# board.net
KiCad netlist of a schematic drawn in EAGLE
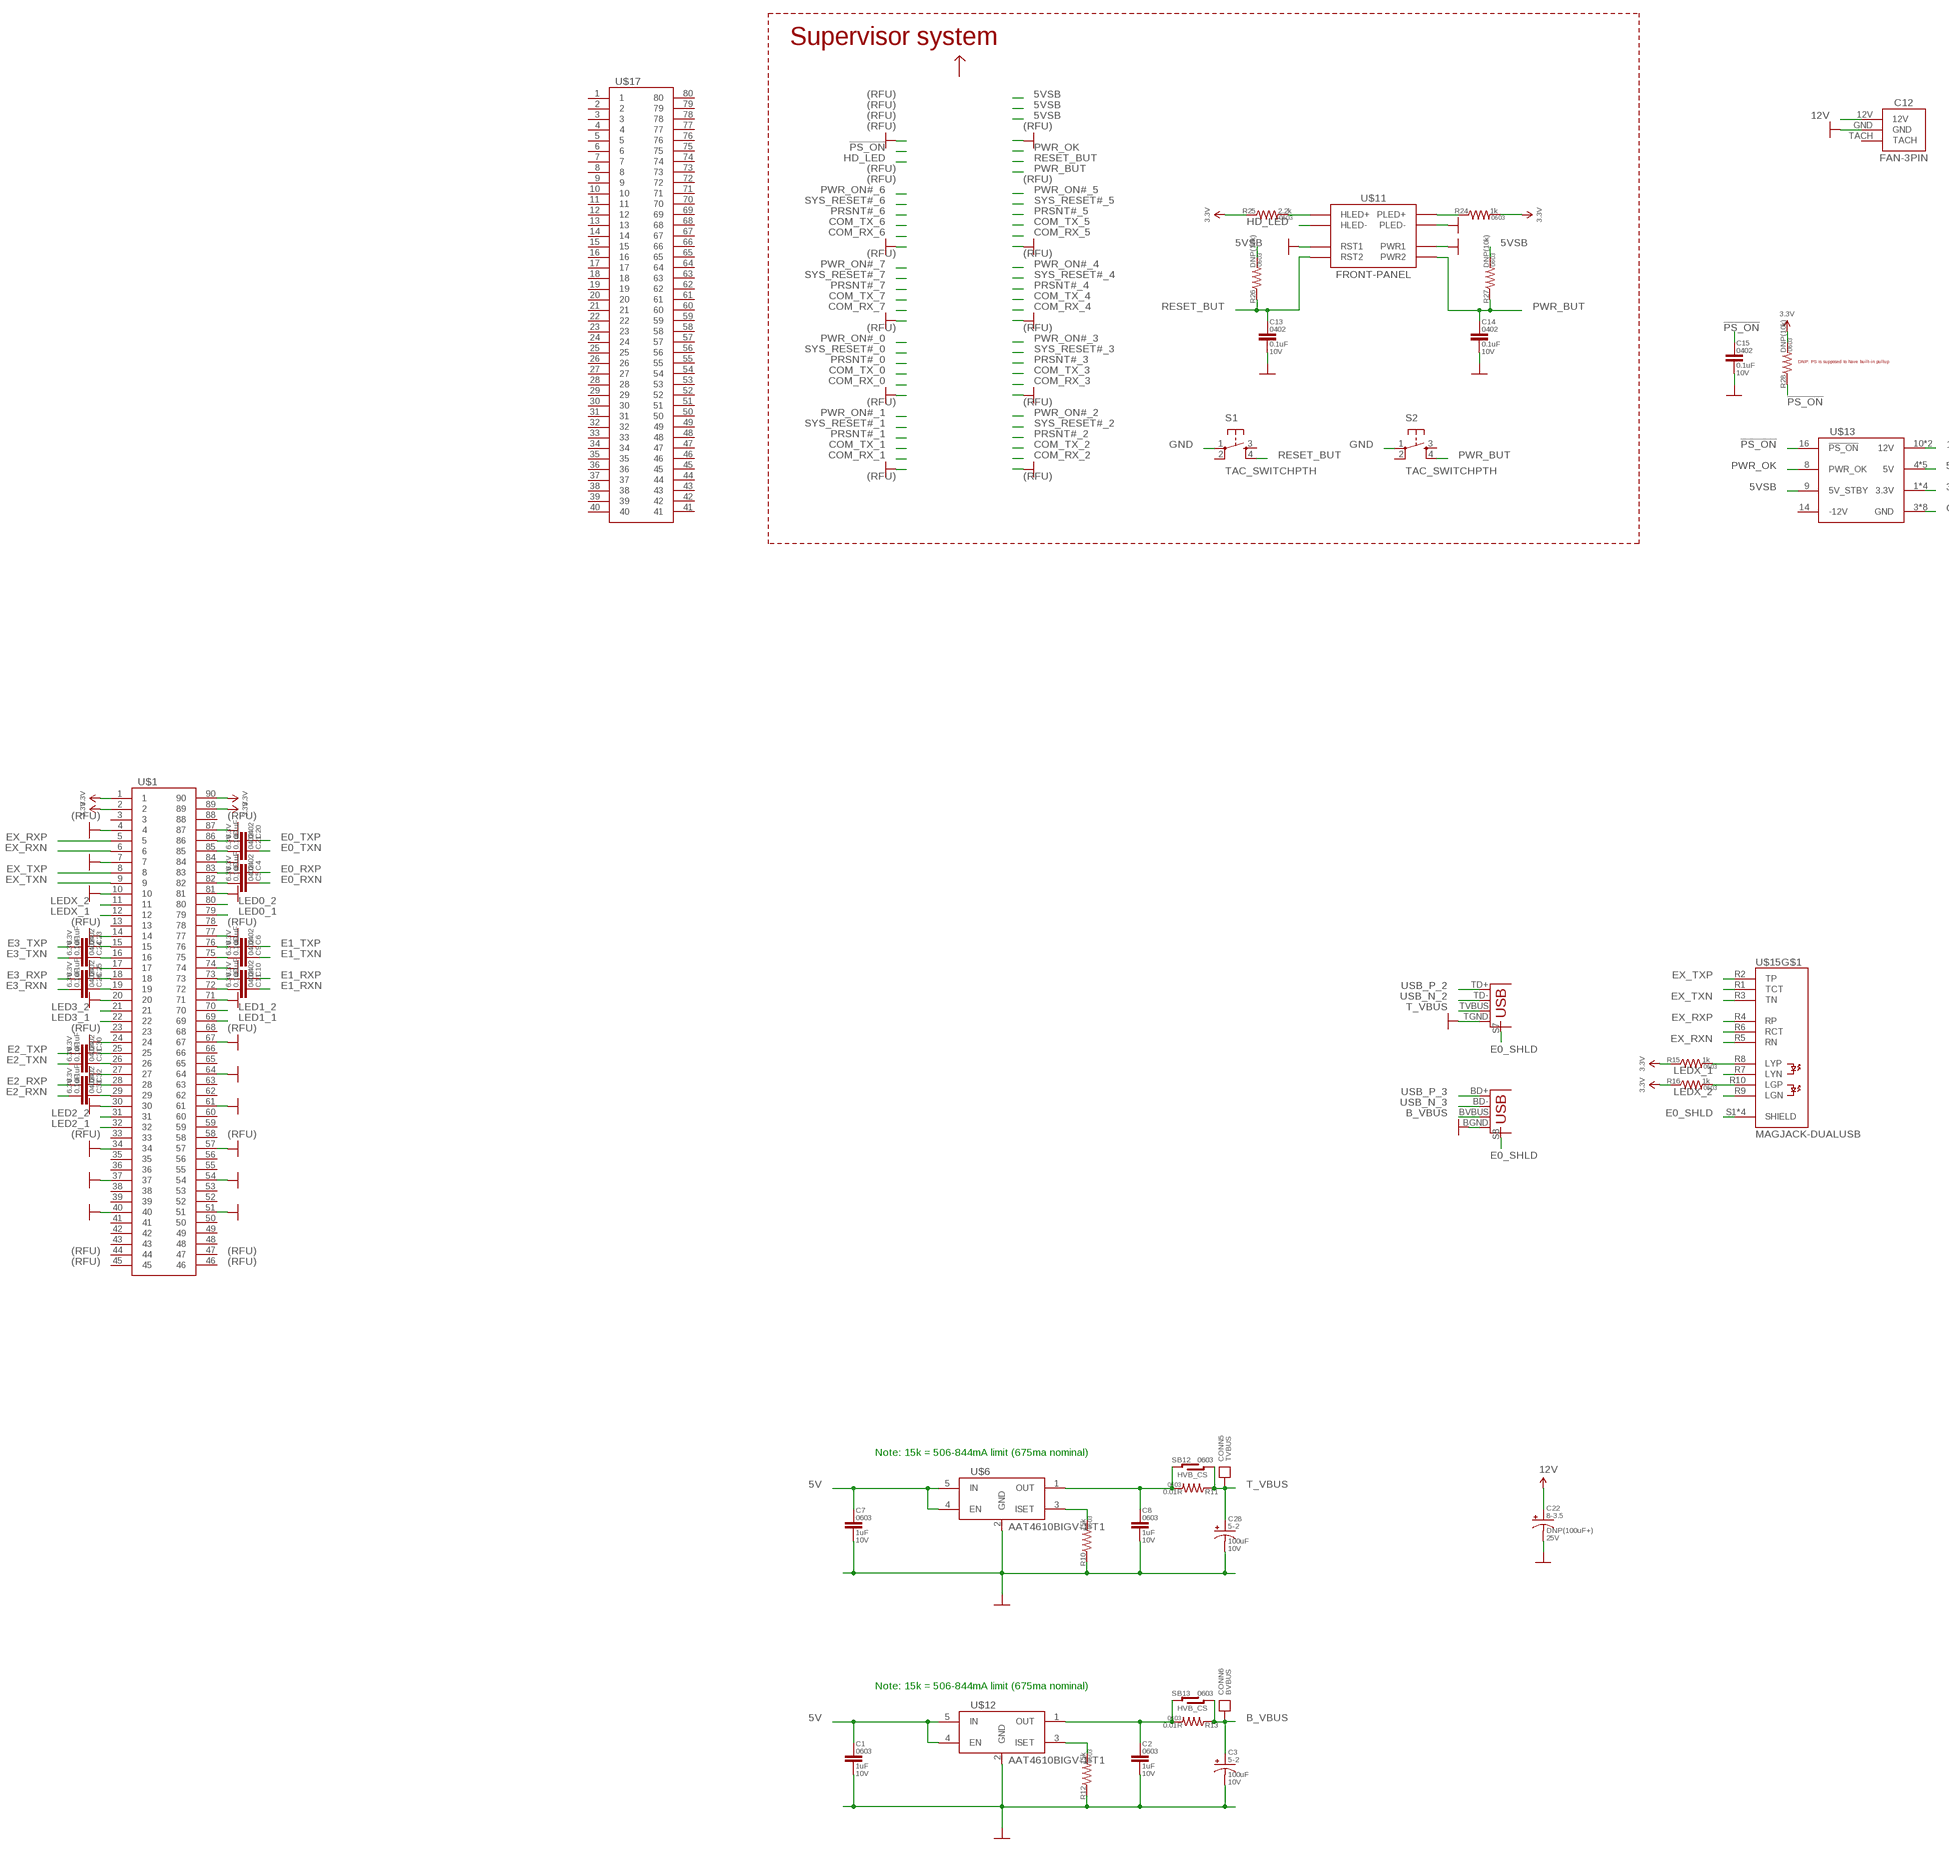
[diagram p0: schematic, sheet 1, part 1 of 2]
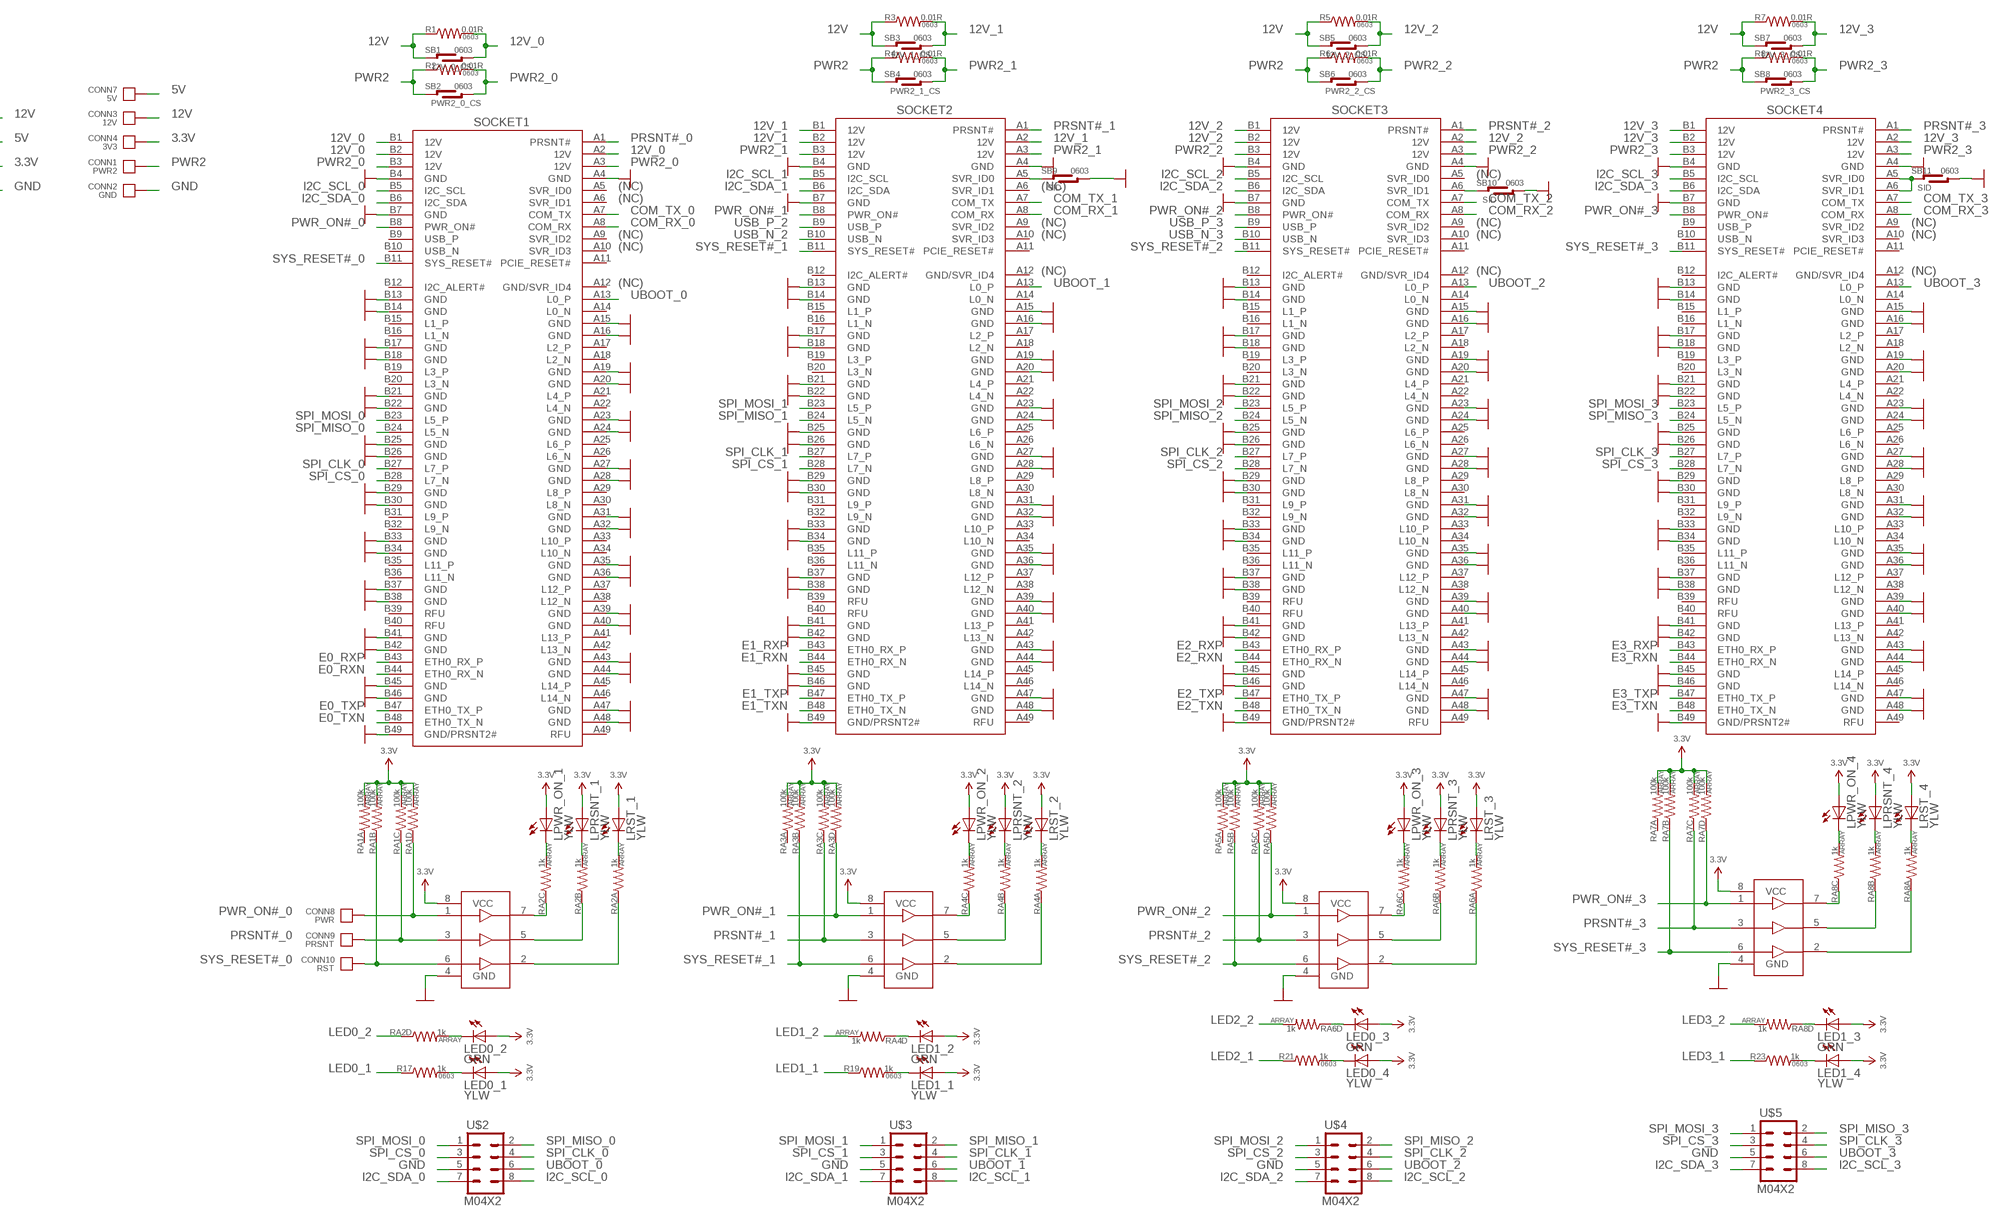
[diagram p1: schematic, sheet 1, part 2 of 2]

(export (version "E")
  (design (tool "Eeschema 10.0.6"))
  (components
    (comp (ref "C1")
      (value "1uF")
      (footprint "eagle-import:0603-CAP")
      (fields (field (name "VOLTAGE") "6.3V") (field (name "VOLTAGE_1") "10V"))
      (libsource (lib "eagle-import") (part "CAP0603"))
    )
    (comp (ref "C2")
      (value "1uF")
      (footprint "eagle-import:0603-CAP")
      (fields (field (name "VOLTAGE") "6.3V") (field (name "VOLTAGE_1") "10V"))
      (libsource (lib "eagle-import") (part "CAP0603"))
    )
    (comp (ref "C3")
      (value "100uF")
      (footprint "eagle-import:CAP-5-2")
      (fields (field (name "VOLTAGE") "6.3V") (field (name "VOLTAGE_1") "10V"))
      (libsource (lib "eagle-import") (part "CAP_POLPTH-5-2"))
    )
    (comp (ref "C4")
      (value "0.1uF")
      (footprint "eagle-import:0402-CAP")
      (fields (field (name "VOLTAGE") "6.3V"))
      (libsource (lib "eagle-import") (part "CAP0402-CAP"))
    )
    (comp (ref "C5")
      (value "0.1uF")
      (footprint "eagle-import:0402-CAP")
      (fields (field (name "VOLTAGE") "6.3V"))
      (libsource (lib "eagle-import") (part "CAP0402-CAP"))
    )
    (comp (ref "C6")
      (value "0.1uF")
      (footprint "eagle-import:0402-CAP")
      (fields (field (name "VOLTAGE") "6.3V"))
      (libsource (lib "eagle-import") (part "CAP0402-CAP"))
    )
    (comp (ref "C7")
      (value "1uF")
      (footprint "eagle-import:0603-CAP")
      (fields (field (name "VOLTAGE") "6.3V") (field (name "VOLTAGE_1") "10V"))
      (libsource (lib "eagle-import") (part "CAP0603"))
    )
    (comp (ref "C8")
      (value "1uF")
      (footprint "eagle-import:0603-CAP")
      (fields (field (name "VOLTAGE") "6.3V") (field (name "VOLTAGE_1") "10V"))
      (libsource (lib "eagle-import") (part "CAP0603"))
    )
    (comp (ref "C9")
      (value "0.1uF")
      (footprint "eagle-import:0402-CAP")
      (fields (field (name "VOLTAGE") "6.3V"))
      (libsource (lib "eagle-import") (part "CAP0402-CAP"))
    )
    (comp (ref "C10")
      (value "0.1uF")
      (footprint "eagle-import:0402-CAP")
      (fields (field (name "VOLTAGE") "6.3V"))
      (libsource (lib "eagle-import") (part "CAP0402-CAP"))
    )
    (comp (ref "C11")
      (value "0.1uF")
      (footprint "eagle-import:0402-CAP")
      (fields (field (name "VOLTAGE") "6.3V"))
      (libsource (lib "eagle-import") (part "CAP0402-CAP"))
    )
    (comp (ref "C12")
      (value "FAN-3PIN")
      (footprint "eagle-import:FAN-3PIN")
      (libsource (lib "eagle-import") (part "FAN-3PIN"))
    )
    (comp (ref "C13")
      (value "0.1uF")
      (footprint "eagle-import:0402-CAP")
      (fields (field (name "VOLTAGE") "6.3V") (field (name "VOLTAGE_1") "10V"))
      (libsource (lib "eagle-import") (part "CAP0402-CAP"))
    )
    (comp (ref "C14")
      (value "0.1uF")
      (footprint "eagle-import:0402-CAP")
      (fields (field (name "VOLTAGE") "6.3V") (field (name "VOLTAGE_1") "10V"))
      (libsource (lib "eagle-import") (part "CAP0402-CAP"))
    )
    (comp (ref "C15")
      (value "0.1uF")
      (footprint "eagle-import:0402-CAP")
      (fields (field (name "VOLTAGE") "6.3V") (field (name "VOLTAGE_1") "10V"))
      (libsource (lib "eagle-import") (part "CAP0402-CAP"))
    )
    (comp (ref "C20")
      (value "0.1uF")
      (footprint "eagle-import:0402-CAP")
      (fields (field (name "VOLTAGE") "6.3V"))
      (libsource (lib "eagle-import") (part "CAP0402-CAP"))
    )
    (comp (ref "C21")
      (value "0.1uF")
      (footprint "eagle-import:0402-CAP")
      (fields (field (name "VOLTAGE") "6.3V"))
      (libsource (lib "eagle-import") (part "CAP0402-CAP"))
    )
    (comp (ref "C22")
      (value "DNP(100uF+)")
      (footprint "eagle-import:CAP-8-3.5")
      (fields (field (name "VOLTAGE") "6.3V") (field (name "VOLTAGE_1") "25V"))
      (libsource (lib "eagle-import") (part "CAP_POLPTH-8-3.5"))
    )
    (comp (ref "C23")
      (value "0.1uF")
      (footprint "eagle-import:0402-CAP")
      (fields (field (name "VOLTAGE") "6.3V"))
      (libsource (lib "eagle-import") (part "CAP0402-CAP"))
    )
    (comp (ref "C24")
      (value "0.1uF")
      (footprint "eagle-import:0402-CAP")
      (fields (field (name "VOLTAGE") "6.3V"))
      (libsource (lib "eagle-import") (part "CAP0402-CAP"))
    )
    (comp (ref "C25")
      (value "0.1uF")
      (footprint "eagle-import:0402-CAP")
      (fields (field (name "VOLTAGE") "6.3V"))
      (libsource (lib "eagle-import") (part "CAP0402-CAP"))
    )
    (comp (ref "C26")
      (value "0.1uF")
      (footprint "eagle-import:0402-CAP")
      (fields (field (name "VOLTAGE") "6.3V"))
      (libsource (lib "eagle-import") (part "CAP0402-CAP"))
    )
    (comp (ref "C28")
      (value "100uF")
      (footprint "eagle-import:CAP-5-2")
      (fields (field (name "VOLTAGE") "6.3V") (field (name "VOLTAGE_1") "10V"))
      (libsource (lib "eagle-import") (part "CAP_POLPTH-5-2"))
    )
    (comp (ref "C30")
      (value "0.1uF")
      (footprint "eagle-import:0402-CAP")
      (fields (field (name "VOLTAGE") "6.3V"))
      (libsource (lib "eagle-import") (part "CAP0402-CAP"))
    )
    (comp (ref "C31")
      (value "0.1uF")
      (footprint "eagle-import:0402-CAP")
      (fields (field (name "VOLTAGE") "6.3V"))
      (libsource (lib "eagle-import") (part "CAP0402-CAP"))
    )
    (comp (ref "C32")
      (value "0.1uF")
      (footprint "eagle-import:0402-CAP")
      (fields (field (name "VOLTAGE") "6.3V"))
      (libsource (lib "eagle-import") (part "CAP0402-CAP"))
    )
    (comp (ref "C33")
      (value "0.1uF")
      (footprint "eagle-import:0402-CAP")
      (fields (field (name "VOLTAGE") "6.3V"))
      (libsource (lib "eagle-import") (part "CAP0402-CAP"))
    )
    (comp (ref "CONN1")
      (value "PWR2")
      (footprint "eagle-import:HOLE_18AWG")
      (libsource (lib "eagle-import") (part "CONNECTOR18AWG"))
    )
    (comp (ref "CONN2")
      (value "GND")
      (footprint "eagle-import:HOLE_18AWG")
      (libsource (lib "eagle-import") (part "CONNECTOR18AWG"))
    )
    (comp (ref "CONN3")
      (value "12V")
      (footprint "eagle-import:HOLE_18AWG")
      (libsource (lib "eagle-import") (part "CONNECTOR18AWG"))
    )
    (comp (ref "CONN4")
      (value "3V3")
      (footprint "eagle-import:HOLE_18AWG")
      (libsource (lib "eagle-import") (part "CONNECTOR18AWG"))
    )
    (comp (ref "CONN5")
      (value "TVBUS")
      (footprint "eagle-import:HOLE_22AWG")
      (libsource (lib "eagle-import") (part "CONNECTOR22AWG"))
    )
    (comp (ref "CONN6")
      (value "BVBUS")
      (footprint "eagle-import:HOLE_22AWG")
      (libsource (lib "eagle-import") (part "CONNECTOR22AWG"))
    )
    (comp (ref "CONN7")
      (value "5V")
      (footprint "eagle-import:HOLE_18AWG")
      (libsource (lib "eagle-import") (part "CONNECTOR18AWG"))
    )
    (comp (ref "CONN8")
      (value "PWR")
      (footprint "eagle-import:TESTPAD-1.27")
      (libsource (lib "eagle-import") (part "CONNECTOR1.27"))
    )
    (comp (ref "CONN9")
      (value "PRSNT")
      (footprint "eagle-import:TESTPAD-1.27")
      (libsource (lib "eagle-import") (part "CONNECTOR1.27"))
    )
    (comp (ref "CONN10")
      (value "RST")
      (footprint "eagle-import:TESTPAD-1.27")
      (libsource (lib "eagle-import") (part "CONNECTOR1.27"))
    )
    (comp (ref "IC1")
      (value "74X3G34")
      (footprint "eagle-import:TSSOP8")
      (libsource (lib "eagle-import") (part "74X3G34"))
    )
    (comp (ref "IC2")
      (value "74X3G34")
      (footprint "eagle-import:TSSOP8")
      (libsource (lib "eagle-import") (part "74X3G34"))
    )
    (comp (ref "IC3")
      (value "74X3G34")
      (footprint "eagle-import:TSSOP8")
      (libsource (lib "eagle-import") (part "74X3G34"))
    )
    (comp (ref "IC4")
      (value "74X3G34")
      (footprint "eagle-import:TSSOP8")
      (libsource (lib "eagle-import") (part "74X3G34"))
    )
    (comp (ref "LED0_1")
      (value "YLW")
      (footprint "eagle-import:0603_LED")
      (libsource (lib "eagle-import") (part "LED0603"))
    )
    (comp (ref "LED0_2")
      (value "GRN")
      (footprint "eagle-import:0603_LED")
      (libsource (lib "eagle-import") (part "LED0603"))
    )
    (comp (ref "LED0_3")
      (value "GRN")
      (footprint "eagle-import:0603_LED")
      (libsource (lib "eagle-import") (part "LED0603"))
    )
    (comp (ref "LED0_4")
      (value "YLW")
      (footprint "eagle-import:0603_LED")
      (libsource (lib "eagle-import") (part "LED0603"))
    )
    (comp (ref "LED1_1")
      (value "YLW")
      (footprint "eagle-import:0603_LED")
      (libsource (lib "eagle-import") (part "LED0603"))
    )
    (comp (ref "LED1_2")
      (value "GRN")
      (footprint "eagle-import:0603_LED")
      (libsource (lib "eagle-import") (part "LED0603"))
    )
    (comp (ref "LED1_3")
      (value "GRN")
      (footprint "eagle-import:0603_LED")
      (libsource (lib "eagle-import") (part "LED0603"))
    )
    (comp (ref "LED1_4")
      (value "YLW")
      (footprint "eagle-import:0603_LED")
      (libsource (lib "eagle-import") (part "LED0603"))
    )
    (comp (ref "LPRSNT_1")
      (value "YLW")
      (footprint "eagle-import:0603_LED")
      (libsource (lib "eagle-import") (part "LED0603"))
    )
    (comp (ref "LPRSNT_2")
      (value "YLW")
      (footprint "eagle-import:0603_LED")
      (libsource (lib "eagle-import") (part "LED0603"))
    )
    (comp (ref "LPRSNT_3")
      (value "YLW")
      (footprint "eagle-import:0603_LED")
      (libsource (lib "eagle-import") (part "LED0603"))
    )
    (comp (ref "LPRSNT_4")
      (value "YLW")
      (footprint "eagle-import:0603_LED")
      (libsource (lib "eagle-import") (part "LED0603"))
    )
    (comp (ref "LPWR_ON_1")
      (value "YLW")
      (footprint "eagle-import:0603_LED")
      (libsource (lib "eagle-import") (part "LED0603"))
    )
    (comp (ref "LPWR_ON_2")
      (value "YLW")
      (footprint "eagle-import:0603_LED")
      (libsource (lib "eagle-import") (part "LED0603"))
    )
    (comp (ref "LPWR_ON_3")
      (value "YLW")
      (footprint "eagle-import:0603_LED")
      (libsource (lib "eagle-import") (part "LED0603"))
    )
    (comp (ref "LPWR_ON_4")
      (value "YLW")
      (footprint "eagle-import:0603_LED")
      (libsource (lib "eagle-import") (part "LED0603"))
    )
    (comp (ref "LRST_1")
      (value "YLW")
      (footprint "eagle-import:0603_LED")
      (libsource (lib "eagle-import") (part "LED0603"))
    )
    (comp (ref "LRST_2")
      (value "YLW")
      (footprint "eagle-import:0603_LED")
      (libsource (lib "eagle-import") (part "LED0603"))
    )
    (comp (ref "LRST_3")
      (value "YLW")
      (footprint "eagle-import:0603_LED")
      (libsource (lib "eagle-import") (part "LED0603"))
    )
    (comp (ref "LRST_4")
      (value "YLW")
      (footprint "eagle-import:0603_LED")
      (libsource (lib "eagle-import") (part "LED0603"))
    )
    (comp (ref "R1")
      (value "0.01R")
      (footprint "eagle-import:0603-RES")
      (libsource (lib "eagle-import") (part "RESISTOR0603"))
    )
    (comp (ref "R2")
      (value "0.01R")
      (footprint "eagle-import:0603-RES")
      (libsource (lib "eagle-import") (part "RESISTOR0603"))
    )
    (comp (ref "R3")
      (value "0.01R")
      (footprint "eagle-import:0603-RES")
      (libsource (lib "eagle-import") (part "RESISTOR0603"))
    )
    (comp (ref "R4")
      (value "0.01R")
      (footprint "eagle-import:0603-RES")
      (libsource (lib "eagle-import") (part "RESISTOR0603"))
    )
    (comp (ref "R5")
      (value "0.01R")
      (footprint "eagle-import:0603-RES")
      (libsource (lib "eagle-import") (part "RESISTOR0603"))
    )
    (comp (ref "R6")
      (value "0.01R")
      (footprint "eagle-import:0603-RES")
      (libsource (lib "eagle-import") (part "RESISTOR0603"))
    )
    (comp (ref "R7")
      (value "0.01R")
      (footprint "eagle-import:0603-RES")
      (libsource (lib "eagle-import") (part "RESISTOR0603"))
    )
    (comp (ref "R8")
      (value "0.01R")
      (footprint "eagle-import:0603-RES")
      (libsource (lib "eagle-import") (part "RESISTOR0603"))
    )
    (comp (ref "R10")
      (value "15k")
      (footprint "eagle-import:0603-RES")
      (libsource (lib "eagle-import") (part "RESISTOR0603"))
    )
    (comp (ref "R11")
      (value "0.01R")
      (footprint "eagle-import:0603-RES")
      (libsource (lib "eagle-import") (part "RESISTOR0603"))
    )
    (comp (ref "R12")
      (value "15k")
      (footprint "eagle-import:0603-RES")
      (libsource (lib "eagle-import") (part "RESISTOR0603"))
    )
    (comp (ref "R13")
      (value "0.01R")
      (footprint "eagle-import:0603-RES")
      (libsource (lib "eagle-import") (part "RESISTOR0603"))
    )
    (comp (ref "R15")
      (value "1k")
      (footprint "eagle-import:0603-RES")
      (libsource (lib "eagle-import") (part "RESISTOR0603"))
    )
    (comp (ref "R16")
      (value "1k")
      (footprint "eagle-import:0603-RES")
      (libsource (lib "eagle-import") (part "RESISTOR0603"))
    )
    (comp (ref "R17")
      (value "1k")
      (footprint "eagle-import:0603-RES")
      (libsource (lib "eagle-import") (part "RESISTOR0603"))
    )
    (comp (ref "R19")
      (value "1k")
      (footprint "eagle-import:0603-RES")
      (libsource (lib "eagle-import") (part "RESISTOR0603"))
    )
    (comp (ref "R21")
      (value "1k")
      (footprint "eagle-import:0603-RES")
      (libsource (lib "eagle-import") (part "RESISTOR0603"))
    )
    (comp (ref "R23")
      (value "1k")
      (footprint "eagle-import:0603-RES")
      (libsource (lib "eagle-import") (part "RESISTOR0603"))
    )
    (comp (ref "R24")
      (value "1k")
      (footprint "eagle-import:0603-RES")
      (libsource (lib "eagle-import") (part "RESISTOR0603"))
    )
    (comp (ref "R25")
      (value "2.2k")
      (footprint "eagle-import:0603-RES")
      (libsource (lib "eagle-import") (part "RESISTOR0603"))
    )
    (comp (ref "R26")
      (value "DNP(10k)")
      (footprint "eagle-import:0603-RES")
      (libsource (lib "eagle-import") (part "RESISTOR0603"))
    )
    (comp (ref "R27")
      (value "DNP(10k)")
      (footprint "eagle-import:0603-RES")
      (libsource (lib "eagle-import") (part "RESISTOR0603"))
    )
    (comp (ref "R28")
      (value "DNP(10k)")
      (footprint "eagle-import:0603-RES")
      (libsource (lib "eagle-import") (part "RESISTOR0603"))
    )
    (comp (ref "RA1")
      (value "100k")
      (footprint "eagle-import:0603-ARV")
      (libsource (lib "eagle-import") (part "RESISTOR_ARRAY0603_X4"))
    )
    (comp (ref "RA2")
      (value "1k")
      (footprint "eagle-import:0603-ARV")
      (libsource (lib "eagle-import") (part "RESISTOR_ARRAY0603_X4"))
    )
    (comp (ref "RA3")
      (value "100k")
      (footprint "eagle-import:0603-ARV")
      (libsource (lib "eagle-import") (part "RESISTOR_ARRAY0603_X4"))
    )
    (comp (ref "RA4")
      (value "1k")
      (footprint "eagle-import:0603-ARV")
      (libsource (lib "eagle-import") (part "RESISTOR_ARRAY0603_X4"))
    )
    (comp (ref "RA5")
      (value "100k")
      (footprint "eagle-import:0603-ARV")
      (libsource (lib "eagle-import") (part "RESISTOR_ARRAY0603_X4"))
    )
    (comp (ref "RA6")
      (value "1k")
      (footprint "eagle-import:0603-ARV")
      (libsource (lib "eagle-import") (part "RESISTOR_ARRAY0603_X4"))
    )
    (comp (ref "RA7")
      (value "100k")
      (footprint "eagle-import:0603-ARV")
      (libsource (lib "eagle-import") (part "RESISTOR_ARRAY0603_X4"))
    )
    (comp (ref "RA8")
      (value "1k")
      (footprint "eagle-import:0603-ARV")
      (libsource (lib "eagle-import") (part "RESISTOR_ARRAY0603_X4"))
    )
    (comp (ref "S1")
      (value "TAC_SWITCHPTH")
      (footprint "eagle-import:TACTILE-PTH")
      (libsource (lib "eagle-import") (part "TAC_SWITCHPTH"))
    )
    (comp (ref "S2")
      (value "TAC_SWITCHPTH")
      (footprint "eagle-import:TACTILE-PTH")
      (libsource (lib "eagle-import") (part "TAC_SWITCHPTH"))
    )
    (comp (ref "SB1")
      (value "12V_0_CS")
      (footprint "eagle-import:SB-0603")
      (libsource (lib "eagle-import") (part "SOLDER-BRIDGE0603"))
    )
    (comp (ref "SB2")
      (value "PWR2_0_CS")
      (footprint "eagle-import:SB-0603")
      (libsource (lib "eagle-import") (part "SOLDER-BRIDGE0603"))
    )
    (comp (ref "SB3")
      (value "12V_1_CS")
      (footprint "eagle-import:SB-0603")
      (libsource (lib "eagle-import") (part "SOLDER-BRIDGE0603"))
    )
    (comp (ref "SB4")
      (value "PWR2_1_CS")
      (footprint "eagle-import:SB-0603")
      (libsource (lib "eagle-import") (part "SOLDER-BRIDGE0603"))
    )
    (comp (ref "SB5")
      (value "12V_2_CS")
      (footprint "eagle-import:SB-0603")
      (libsource (lib "eagle-import") (part "SOLDER-BRIDGE0603"))
    )
    (comp (ref "SB6")
      (value "PWR2_2_CS")
      (footprint "eagle-import:SB-0603")
      (libsource (lib "eagle-import") (part "SOLDER-BRIDGE0603"))
    )
    (comp (ref "SB7")
      (value "12V_3_CS")
      (footprint "eagle-import:SB-0603")
      (libsource (lib "eagle-import") (part "SOLDER-BRIDGE0603"))
    )
    (comp (ref "SB8")
      (value "PWR2_3_CS")
      (footprint "eagle-import:SB-0603")
      (libsource (lib "eagle-import") (part "SOLDER-BRIDGE0603"))
    )
    (comp (ref "SB9")
      (value "SID")
      (footprint "eagle-import:SB-0603")
      (libsource (lib "eagle-import") (part "SOLDER-BRIDGE0603"))
    )
    (comp (ref "SB10")
      (value "SID")
      (footprint "eagle-import:SB-0603")
      (libsource (lib "eagle-import") (part "SOLDER-BRIDGE0603"))
    )
    (comp (ref "SB11")
      (value "SID")
      (footprint "eagle-import:SB-0603")
      (libsource (lib "eagle-import") (part "SOLDER-BRIDGE0603"))
    )
    (comp (ref "SB12")
      (value "HVB_CS")
      (footprint "eagle-import:SB-0603")
      (libsource (lib "eagle-import") (part "SOLDER-BRIDGE0603"))
    )
    (comp (ref "SB13")
      (value "HVB_CS")
      (footprint "eagle-import:SB-0603")
      (libsource (lib "eagle-import") (part "SOLDER-BRIDGE0603"))
    )
    (comp (ref "SOCKET1")
      (value "COVEN-V1CONN")
      (footprint "eagle-import:CVN-V1-CONN")
      (libsource (lib "eagle-import") (part "COVEN-V1CONN"))
    )
    (comp (ref "SOCKET2")
      (value "COVEN-V1CONN")
      (footprint "eagle-import:CVN-V1-CONN")
      (libsource (lib "eagle-import") (part "COVEN-V1CONN"))
    )
    (comp (ref "SOCKET3")
      (value "COVEN-V1CONN")
      (footprint "eagle-import:CVN-V1-CONN")
      (libsource (lib "eagle-import") (part "COVEN-V1CONN"))
    )
    (comp (ref "SOCKET4")
      (value "COVEN-V1CONN")
      (footprint "eagle-import:CVN-V1-CONN")
      (libsource (lib "eagle-import") (part "COVEN-V1CONN"))
    )
    (comp (ref "U$1")
      (value "DF40-90RCP")
      (footprint "eagle-import:DF40-RCP-90")
      (libsource (lib "eagle-import") (part "DF40-90RCP"))
    )
    (comp (ref "U$2")
      (value "M04X2")
      (footprint "eagle-import:2X4")
      (libsource (lib "eagle-import") (part "M04X2"))
    )
    (comp (ref "U$3")
      (value "M04X2")
      (footprint "eagle-import:2X4")
      (libsource (lib "eagle-import") (part "M04X2"))
    )
    (comp (ref "U$4")
      (value "M04X2")
      (footprint "eagle-import:2X4")
      (libsource (lib "eagle-import") (part "M04X2"))
    )
    (comp (ref "U$5")
      (value "M04X2")
      (footprint "eagle-import:2X4")
      (libsource (lib "eagle-import") (part "M04X2"))
    )
    (comp (ref "U$6")
      (value "AAT4610BIGV-1-T1")
      (footprint "eagle-import:SOT23-5")
      (libsource (lib "eagle-import") (part "LOAD_SWITCH_ILIMIT"))
    )
    (comp (ref "U$11")
      (value "FRONT-PANEL")
      (footprint "eagle-import:FRONT-PANEL")
      (libsource (lib "eagle-import") (part "FRONT-PANEL"))
    )
    (comp (ref "U$12")
      (value "AAT4610BIGV-1-T1")
      (footprint "eagle-import:SOT23-5")
      (libsource (lib "eagle-import") (part "LOAD_SWITCH_ILIMIT"))
    )
    (comp (ref "U$13")
      (value "ATX-PWRVERT")
      (footprint "eagle-import:ATX-24-VERT")
      (libsource (lib "eagle-import") (part "ATX-PWRVERT"))
    )
    (comp (ref "U$15")
      (value "MAGJACK-DUALUSB")
      (footprint "eagle-import:MAGJACK-DUALUSB")
      (libsource (lib "eagle-import") (part "MAGJACK-DUALUSB"))
    )
    (comp (ref "U$17")
      (value "DF40-80RCP")
      (footprint "eagle-import:DF40-RCP-80")
      (libsource (lib "eagle-import") (part "DF40-80RCP"))
    )
  )
  (nets
    (net (code "1") (name "/5V") (class "Default")
      (node (ref "C1") (pin "1") (pinfunction "1_1") (pintype "passive"))
      (node (ref "C7") (pin "1") (pinfunction "1_1") (pintype "passive"))
      (node (ref "CONN7") (pin "P$1") (pinfunction "P_P$1") (pintype "bidirectional"))
      (node (ref "U$12") (pin "4") (pinfunction "EN_4") (pintype "bidirectional"))
      (node (ref "U$12") (pin "5") (pinfunction "IN_5") (pintype "bidirectional"))
      (node (ref "U$13") (pin "21") (pinfunction "5V_21") (pintype "bidirectional"))
      (node (ref "U$13") (pin "22") (pinfunction "5V_22") (pintype "bidirectional"))
      (node (ref "U$13") (pin "23") (pinfunction "5V_23") (pintype "bidirectional"))
      (node (ref "U$13") (pin "4") (pinfunction "5V_4") (pintype "bidirectional"))
      (node (ref "U$13") (pin "6") (pinfunction "5V_6") (pintype "bidirectional"))
      (node (ref "U$6") (pin "4") (pinfunction "EN_4") (pintype "bidirectional"))
      (node (ref "U$6") (pin "5") (pinfunction "IN_5") (pintype "bidirectional"))
    )
    (net (code "2") (name "/5VSB") (class "Default")
      (node (ref "R26") (pin "2") (pinfunction "2_2") (pintype "passive"))
      (node (ref "R27") (pin "2") (pinfunction "2_2") (pintype "passive"))
      (node (ref "U$13") (pin "9") (pinfunction "5V_STBY_9") (pintype "bidirectional"))
    )
    (net (code "3") (name "/12V_0") (class "Default")
      (node (ref "R1") (pin "2") (pinfunction "2_2") (pintype "passive"))
      (node (ref "SB1") (pin "R1") (pinfunction "P$2_R1") (pintype "passive"))
      (node (ref "SB1") (pin "R2") (pinfunction "P$2_R2") (pintype "passive"))
      (node (ref "SOCKET1") (pin "A2") (pinfunction "12V_A2") (pintype "input"))
      (node (ref "SOCKET1") (pin "B1") (pinfunction "12V_B1") (pintype "input"))
      (node (ref "SOCKET1") (pin "B2") (pinfunction "12V_B2") (pintype "input"))
    )
    (net (code "4") (name "/12V_1") (class "Default")
      (node (ref "R3") (pin "2") (pinfunction "2_2") (pintype "passive"))
      (node (ref "SB3") (pin "R1") (pinfunction "P$2_R1") (pintype "passive"))
      (node (ref "SB3") (pin "R2") (pinfunction "P$2_R2") (pintype "passive"))
      (node (ref "SOCKET2") (pin "A2") (pinfunction "12V_A2") (pintype "input"))
      (node (ref "SOCKET2") (pin "B1") (pinfunction "12V_B1") (pintype "input"))
      (node (ref "SOCKET2") (pin "B2") (pinfunction "12V_B2") (pintype "input"))
    )
    (net (code "5") (name "/12V_2") (class "Default")
      (node (ref "R5") (pin "2") (pinfunction "2_2") (pintype "passive"))
      (node (ref "SB5") (pin "R1") (pinfunction "P$2_R1") (pintype "passive"))
      (node (ref "SB5") (pin "R2") (pinfunction "P$2_R2") (pintype "passive"))
      (node (ref "SOCKET3") (pin "A2") (pinfunction "12V_A2") (pintype "input"))
      (node (ref "SOCKET3") (pin "B1") (pinfunction "12V_B1") (pintype "input"))
      (node (ref "SOCKET3") (pin "B2") (pinfunction "12V_B2") (pintype "input"))
    )
    (net (code "6") (name "/12V_3") (class "Default")
      (node (ref "R7") (pin "2") (pinfunction "2_2") (pintype "passive"))
      (node (ref "SB7") (pin "R1") (pinfunction "P$2_R1") (pintype "passive"))
      (node (ref "SB7") (pin "R2") (pinfunction "P$2_R2") (pintype "passive"))
      (node (ref "SOCKET4") (pin "A2") (pinfunction "12V_A2") (pintype "input"))
      (node (ref "SOCKET4") (pin "B1") (pinfunction "12V_B1") (pintype "input"))
      (node (ref "SOCKET4") (pin "B2") (pinfunction "12V_B2") (pintype "input"))
    )
    (net (code "7") (name "/B_VBUS") (class "Default")
      (node (ref "C3") (pin "1") (pinfunction "+_1") (pintype "passive"))
      (node (ref "CONN6") (pin "P") (pinfunction "P_P") (pintype "bidirectional"))
      (node (ref "R13") (pin "1") (pinfunction "1_1") (pintype "passive"))
      (node (ref "SB13") (pin "R1") (pinfunction "P$2_R1") (pintype "passive"))
      (node (ref "SB13") (pin "R2") (pinfunction "P$2_R2") (pintype "passive"))
      (node (ref "U$15") (pin "BVBUS") (pinfunction "VBUS_BVBUS") (pintype "bidirectional"))
    )
    (net (code "8") (name "/COM_RX_0") (class "Default")
      (node (ref "SOCKET1") (pin "A8") (pinfunction "COM_RX_A8") (pintype "bidirectional"))
    )
    (net (code "9") (name "/COM_RX_1") (class "Default")
      (node (ref "SOCKET2") (pin "A8") (pinfunction "COM_RX_A8") (pintype "bidirectional"))
    )
    (net (code "10") (name "/COM_RX_2") (class "Default")
      (node (ref "SOCKET3") (pin "A8") (pinfunction "COM_RX_A8") (pintype "bidirectional"))
    )
    (net (code "11") (name "/COM_RX_3") (class "Default")
      (node (ref "SOCKET4") (pin "A8") (pinfunction "COM_RX_A8") (pintype "bidirectional"))
    )
    (net (code "16") (name "/COM_TX_0") (class "Default")
      (node (ref "SOCKET1") (pin "A7") (pinfunction "COM_TX_A7") (pintype "bidirectional"))
    )
    (net (code "17") (name "/COM_TX_1") (class "Default")
      (node (ref "SOCKET2") (pin "A7") (pinfunction "COM_TX_A7") (pintype "bidirectional"))
    )
    (net (code "18") (name "/COM_TX_2") (class "Default")
      (node (ref "SOCKET3") (pin "A7") (pinfunction "COM_TX_A7") (pintype "bidirectional"))
    )
    (net (code "19") (name "/COM_TX_3") (class "Default")
      (node (ref "SOCKET4") (pin "A7") (pinfunction "COM_TX_A7") (pintype "bidirectional"))
    )
    (net (code "24") (name "/E0_RXN") (class "Default")
      (node (ref "C5") (pin "1") (pinfunction "1_1") (pintype "passive"))
      (node (ref "SOCKET1") (pin "B44") (pinfunction "ETH0_RX_N_B44") (pintype "bidirectional"))
    )
    (net (code "25") (name "/E0_RXP") (class "Default")
      (node (ref "C4") (pin "1") (pinfunction "1_1") (pintype "passive"))
      (node (ref "SOCKET1") (pin "B43") (pinfunction "ETH0_RX_P_B43") (pintype "bidirectional"))
    )
    (net (code "26") (name "/E0_SHLD") (class "Default")
      (node (ref "U$15") (pin "S1") (pinfunction "SHIELD_S1") (pintype "bidirectional"))
      (node (ref "U$15") (pin "S2") (pinfunction "SHIELD_S2") (pintype "bidirectional"))
      (node (ref "U$15") (pin "S3") (pinfunction "SHIELD_S3") (pintype "bidirectional"))
      (node (ref "U$15") (pin "S4") (pinfunction "SHIELD_S4") (pintype "bidirectional"))
      (node (ref "U$15") (pin "S7") (pinfunction "SHELL_S7") (pintype "bidirectional"))
      (node (ref "U$15") (pin "S8") (pinfunction "SHELL_S8") (pintype "bidirectional"))
    )
    (net (code "27") (name "/E0_TXN") (class "Default")
      (node (ref "C21") (pin "1") (pinfunction "1_1") (pintype "passive"))
      (node (ref "SOCKET1") (pin "B48") (pinfunction "ETH0_TX_N_B48") (pintype "bidirectional"))
    )
    (net (code "28") (name "/E0_TXP") (class "Default")
      (node (ref "C20") (pin "1") (pinfunction "1_1") (pintype "passive"))
      (node (ref "SOCKET1") (pin "B47") (pinfunction "ETH0_TX_P_B47") (pintype "bidirectional"))
    )
    (net (code "29") (name "/E1_RXN") (class "Default")
      (node (ref "C11") (pin "1") (pinfunction "1_1") (pintype "passive"))
      (node (ref "SOCKET2") (pin "B44") (pinfunction "ETH0_RX_N_B44") (pintype "bidirectional"))
    )
    (net (code "30") (name "/E1_RXP") (class "Default")
      (node (ref "C10") (pin "1") (pinfunction "1_1") (pintype "passive"))
      (node (ref "SOCKET2") (pin "B43") (pinfunction "ETH0_RX_P_B43") (pintype "bidirectional"))
    )
    (net (code "31") (name "/E1_TXN") (class "Default")
      (node (ref "C9") (pin "1") (pinfunction "1_1") (pintype "passive"))
      (node (ref "SOCKET2") (pin "B48") (pinfunction "ETH0_TX_N_B48") (pintype "bidirectional"))
    )
    (net (code "32") (name "/E1_TXP") (class "Default")
      (node (ref "C6") (pin "1") (pinfunction "1_1") (pintype "passive"))
      (node (ref "SOCKET2") (pin "B47") (pinfunction "ETH0_TX_P_B47") (pintype "bidirectional"))
    )
    (net (code "33") (name "/E2_RXN") (class "Default")
      (node (ref "C33") (pin "2") (pinfunction "2_2") (pintype "passive"))
      (node (ref "SOCKET3") (pin "B44") (pinfunction "ETH0_RX_N_B44") (pintype "bidirectional"))
    )
    (net (code "34") (name "/E2_RXP") (class "Default")
      (node (ref "C32") (pin "2") (pinfunction "2_2") (pintype "passive"))
      (node (ref "SOCKET3") (pin "B43") (pinfunction "ETH0_RX_P_B43") (pintype "bidirectional"))
    )
    (net (code "35") (name "/E2_TXN") (class "Default")
      (node (ref "C31") (pin "2") (pinfunction "2_2") (pintype "passive"))
      (node (ref "SOCKET3") (pin "B48") (pinfunction "ETH0_TX_N_B48") (pintype "bidirectional"))
    )
    (net (code "36") (name "/E2_TXP") (class "Default")
      (node (ref "C30") (pin "2") (pinfunction "2_2") (pintype "passive"))
      (node (ref "SOCKET3") (pin "B47") (pinfunction "ETH0_TX_P_B47") (pintype "bidirectional"))
    )
    (net (code "37") (name "/E3_RXN") (class "Default")
      (node (ref "C26") (pin "2") (pinfunction "2_2") (pintype "passive"))
      (node (ref "SOCKET4") (pin "B44") (pinfunction "ETH0_RX_N_B44") (pintype "bidirectional"))
    )
    (net (code "38") (name "/E3_RXP") (class "Default")
      (node (ref "C25") (pin "2") (pinfunction "2_2") (pintype "passive"))
      (node (ref "SOCKET4") (pin "B43") (pinfunction "ETH0_RX_P_B43") (pintype "bidirectional"))
    )
    (net (code "39") (name "/E3_TXN") (class "Default")
      (node (ref "C24") (pin "2") (pinfunction "2_2") (pintype "passive"))
      (node (ref "SOCKET4") (pin "B48") (pinfunction "ETH0_TX_N_B48") (pintype "bidirectional"))
    )
    (net (code "40") (name "/E3_TXP") (class "Default")
      (node (ref "C23") (pin "2") (pinfunction "2_2") (pintype "passive"))
      (node (ref "SOCKET4") (pin "B47") (pinfunction "ETH0_TX_P_B47") (pintype "bidirectional"))
    )
    (net (code "41") (name "/EX_RXN") (class "Default")
      (node (ref "U$1") (pin "6") (pinfunction "6_6") (pintype "bidirectional"))
      (node (ref "U$15") (pin "R5") (pinfunction "RN_R5") (pintype "bidirectional"))
    )
    (net (code "42") (name "/EX_RXP") (class "Default")
      (node (ref "U$1") (pin "5") (pinfunction "5_5") (pintype "bidirectional"))
      (node (ref "U$15") (pin "R4") (pinfunction "RP_R4") (pintype "bidirectional"))
    )
    (net (code "43") (name "/EX_TXN") (class "Default")
      (node (ref "U$1") (pin "9") (pinfunction "9_9") (pintype "bidirectional"))
      (node (ref "U$15") (pin "R3") (pinfunction "TN_R3") (pintype "bidirectional"))
    )
    (net (code "44") (name "/EX_TXP") (class "Default")
      (node (ref "U$1") (pin "8") (pinfunction "8_8") (pintype "bidirectional"))
      (node (ref "U$15") (pin "R2") (pinfunction "TP_R2") (pintype "bidirectional"))
    )
    (net (code "45") (name "/HD_LED") (class "Default")
      (node (ref "U$11") (pin "HDLED-") (pinfunction "HLED-_HDLED-") (pintype "bidirectional"))
    )
    (net (code "46") (name "/I2C_SCL_0") (class "Default")
      (node (ref "SOCKET1") (pin "B5") (pinfunction "I2C_SCL_B5") (pintype "bidirectional"))
      (node (ref "U$2") (pin "8") (pinfunction "8_8") (pintype "passive"))
    )
    (net (code "47") (name "/I2C_SCL_1") (class "Default")
      (node (ref "SOCKET2") (pin "B5") (pinfunction "I2C_SCL_B5") (pintype "bidirectional"))
      (node (ref "U$3") (pin "8") (pinfunction "8_8") (pintype "passive"))
    )
    (net (code "48") (name "/I2C_SCL_2") (class "Default")
      (node (ref "SOCKET3") (pin "B5") (pinfunction "I2C_SCL_B5") (pintype "bidirectional"))
      (node (ref "U$4") (pin "8") (pinfunction "8_8") (pintype "passive"))
    )
    (net (code "49") (name "/I2C_SCL_3") (class "Default")
      (node (ref "SOCKET4") (pin "B5") (pinfunction "I2C_SCL_B5") (pintype "bidirectional"))
      (node (ref "U$5") (pin "8") (pinfunction "8_8") (pintype "passive"))
    )
    (net (code "50") (name "/I2C_SDA_0") (class "Default")
      (node (ref "SOCKET1") (pin "B6") (pinfunction "I2C_SDA_B6") (pintype "bidirectional"))
      (node (ref "U$2") (pin "7") (pinfunction "7_7") (pintype "passive"))
    )
    (net (code "51") (name "/I2C_SDA_1") (class "Default")
      (node (ref "SOCKET2") (pin "B6") (pinfunction "I2C_SDA_B6") (pintype "bidirectional"))
      (node (ref "U$3") (pin "7") (pinfunction "7_7") (pintype "passive"))
    )
    (net (code "52") (name "/I2C_SDA_2") (class "Default")
      (node (ref "SOCKET3") (pin "B6") (pinfunction "I2C_SDA_B6") (pintype "bidirectional"))
      (node (ref "U$4") (pin "7") (pinfunction "7_7") (pintype "passive"))
    )
    (net (code "53") (name "/I2C_SDA_3") (class "Default")
      (node (ref "SOCKET4") (pin "B6") (pinfunction "I2C_SDA_B6") (pintype "bidirectional"))
      (node (ref "U$5") (pin "7") (pinfunction "7_7") (pintype "passive"))
    )
    (net (code "54") (name "/LED0_1") (class "Default")
      (node (ref "R17") (pin "1") (pinfunction "1_1") (pintype "passive"))
      (node (ref "U$1") (pin "79") (pinfunction "79_79") (pintype "bidirectional"))
    )
    (net (code "55") (name "/LED0_2") (class "Default")
      (node (ref "RA2") (pin "4") (pinfunction "1_4") (pintype "passive"))
      (node (ref "U$1") (pin "80") (pinfunction "80_80") (pintype "bidirectional"))
    )
    (net (code "56") (name "/LED1_1") (class "Default")
      (node (ref "R19") (pin "1") (pinfunction "1_1") (pintype "passive"))
      (node (ref "U$1") (pin "69") (pinfunction "69_69") (pintype "bidirectional"))
    )
    (net (code "57") (name "/LED1_2") (class "Default")
      (node (ref "RA4") (pin "5") (pinfunction "2_5") (pintype "passive"))
      (node (ref "U$1") (pin "70") (pinfunction "70_70") (pintype "bidirectional"))
    )
    (net (code "58") (name "/LED2_1") (class "Default")
      (node (ref "R21") (pin "1") (pinfunction "1_1") (pintype "passive"))
      (node (ref "U$1") (pin "32") (pinfunction "32_32") (pintype "bidirectional"))
    )
    (net (code "59") (name "/LED2_2") (class "Default")
      (node (ref "RA6") (pin "5") (pinfunction "2_5") (pintype "passive"))
      (node (ref "U$1") (pin "31") (pinfunction "31_31") (pintype "bidirectional"))
    )
    (net (code "60") (name "/LED3_1") (class "Default")
      (node (ref "R23") (pin "1") (pinfunction "1_1") (pintype "passive"))
      (node (ref "U$1") (pin "22") (pinfunction "22_22") (pintype "bidirectional"))
    )
    (net (code "61") (name "/LED3_2") (class "Default")
      (node (ref "RA8") (pin "5") (pinfunction "2_5") (pintype "passive"))
      (node (ref "U$1") (pin "21") (pinfunction "21_21") (pintype "bidirectional"))
    )
    (net (code "62") (name "/LEDX_1") (class "Default")
      (node (ref "U$1") (pin "12") (pinfunction "12_12") (pintype "bidirectional"))
      (node (ref "U$15") (pin "R7") (pinfunction "LYN_R7") (pintype "bidirectional"))
    )
    (net (code "63") (name "/LEDX_2") (class "Default")
      (node (ref "U$1") (pin "11") (pinfunction "11_11") (pintype "bidirectional"))
      (node (ref "U$15") (pin "R9") (pinfunction "LGN_R9") (pintype "bidirectional"))
    )
    (net (code "64") (name "/PRSNT#_0") (class "Default")
      (node (ref "CONN9") (pin "P") (pinfunction "P_P") (pintype "bidirectional"))
      (node (ref "IC1") (pin "3") (pinfunction "2A_3") (pintype "bidirectional"))
      (node (ref "RA1") (pin "3") (pinfunction "1_3") (pintype "passive"))
      (node (ref "SOCKET1") (pin "A1") (pinfunction "PRSNT#_A1") (pintype "bidirectional"))
    )
    (net (code "65") (name "/PRSNT#_1") (class "Default")
      (node (ref "IC2") (pin "3") (pinfunction "2A_3") (pintype "bidirectional"))
      (node (ref "RA3") (pin "3") (pinfunction "1_3") (pintype "passive"))
      (node (ref "SOCKET2") (pin "A1") (pinfunction "PRSNT#_A1") (pintype "bidirectional"))
    )
    (net (code "66") (name "/PRSNT#_2") (class "Default")
      (node (ref "IC3") (pin "3") (pinfunction "2A_3") (pintype "bidirectional"))
      (node (ref "RA5") (pin "3") (pinfunction "1_3") (pintype "passive"))
      (node (ref "SOCKET3") (pin "A1") (pinfunction "PRSNT#_A1") (pintype "bidirectional"))
    )
    (net (code "67") (name "/PRSNT#_3") (class "Default")
      (node (ref "IC4") (pin "3") (pinfunction "2A_3") (pintype "bidirectional"))
      (node (ref "RA7") (pin "3") (pinfunction "1_3") (pintype "passive"))
      (node (ref "SOCKET4") (pin "A1") (pinfunction "PRSNT#_A1") (pintype "bidirectional"))
    )
    (net (code "72") (name "/PWR2") (class "Default")
      (node (ref "CONN1") (pin "P$1") (pinfunction "P_P$1") (pintype "bidirectional"))
      (node (ref "R2") (pin "1") (pinfunction "1_1") (pintype "passive"))
      (node (ref "R4") (pin "1") (pinfunction "1_1") (pintype "passive"))
      (node (ref "R6") (pin "1") (pinfunction "1_1") (pintype "passive"))
      (node (ref "R8") (pin "1") (pinfunction "1_1") (pintype "passive"))
      (node (ref "SB2") (pin "L1") (pinfunction "P$1_L1") (pintype "passive"))
      (node (ref "SB2") (pin "L2") (pinfunction "P$1_L2") (pintype "passive"))
      (node (ref "SB4") (pin "L1") (pinfunction "P$1_L1") (pintype "passive"))
      (node (ref "SB4") (pin "L2") (pinfunction "P$1_L2") (pintype "passive"))
      (node (ref "SB6") (pin "L1") (pinfunction "P$1_L1") (pintype "passive"))
      (node (ref "SB6") (pin "L2") (pinfunction "P$1_L2") (pintype "passive"))
      (node (ref "SB8") (pin "L1") (pinfunction "P$1_L1") (pintype "passive"))
      (node (ref "SB8") (pin "L2") (pinfunction "P$1_L2") (pintype "passive"))
    )
    (net (code "73") (name "/PWR2_0") (class "Default")
      (node (ref "R2") (pin "2") (pinfunction "2_2") (pintype "passive"))
      (node (ref "SB2") (pin "R1") (pinfunction "P$2_R1") (pintype "passive"))
      (node (ref "SB2") (pin "R2") (pinfunction "P$2_R2") (pintype "passive"))
      (node (ref "SOCKET1") (pin "A3") (pinfunction "12V_A3") (pintype "input"))
      (node (ref "SOCKET1") (pin "B3") (pinfunction "12V_B3") (pintype "input"))
    )
    (net (code "74") (name "/PWR2_1") (class "Default")
      (node (ref "R4") (pin "2") (pinfunction "2_2") (pintype "passive"))
      (node (ref "SB4") (pin "R1") (pinfunction "P$2_R1") (pintype "passive"))
      (node (ref "SB4") (pin "R2") (pinfunction "P$2_R2") (pintype "passive"))
      (node (ref "SOCKET2") (pin "A3") (pinfunction "12V_A3") (pintype "input"))
      (node (ref "SOCKET2") (pin "B3") (pinfunction "12V_B3") (pintype "input"))
    )
    (net (code "75") (name "/PWR2_2") (class "Default")
      (node (ref "R6") (pin "2") (pinfunction "2_2") (pintype "passive"))
      (node (ref "SB6") (pin "R1") (pinfunction "P$2_R1") (pintype "passive"))
      (node (ref "SB6") (pin "R2") (pinfunction "P$2_R2") (pintype "passive"))
      (node (ref "SOCKET3") (pin "A3") (pinfunction "12V_A3") (pintype "input"))
      (node (ref "SOCKET3") (pin "B3") (pinfunction "12V_B3") (pintype "input"))
    )
    (net (code "76") (name "/PWR2_3") (class "Default")
      (node (ref "R8") (pin "2") (pinfunction "2_2") (pintype "passive"))
      (node (ref "SB8") (pin "R1") (pinfunction "P$2_R1") (pintype "passive"))
      (node (ref "SB8") (pin "R2") (pinfunction "P$2_R2") (pintype "passive"))
      (node (ref "SOCKET4") (pin "A3") (pinfunction "12V_A3") (pintype "input"))
      (node (ref "SOCKET4") (pin "B3") (pinfunction "12V_B3") (pintype "input"))
    )
    (net (code "77") (name "/PWR_BUT") (class "Default")
      (node (ref "C14") (pin "1") (pinfunction "1_1") (pintype "passive"))
      (node (ref "R27") (pin "1") (pinfunction "1_1") (pintype "passive"))
      (node (ref "S2") (pin "4") (pinfunction "4_4") (pintype "passive"))
      (node (ref "U$11") (pin "PWR_2") (pinfunction "PWR2_PWR_2") (pintype "bidirectional"))
    )
    (net (code "78") (name "/PWR_OK") (class "Default")
      (node (ref "U$13") (pin "8") (pinfunction "PWR_OK_8") (pintype "bidirectional"))
    )
    (net (code "79") (name "/PWR_ON#_0") (class "Default")
      (node (ref "CONN8") (pin "P") (pinfunction "P_P") (pintype "bidirectional"))
      (node (ref "IC1") (pin "1") (pinfunction "1A_1") (pintype "bidirectional"))
      (node (ref "RA1") (pin "4") (pinfunction "1_4") (pintype "passive"))
      (node (ref "SOCKET1") (pin "B8") (pinfunction "PWR_ON#_B8") (pintype "bidirectional"))
    )
    (net (code "80") (name "/PWR_ON#_1") (class "Default")
      (node (ref "IC2") (pin "1") (pinfunction "1A_1") (pintype "bidirectional"))
      (node (ref "RA3") (pin "4") (pinfunction "1_4") (pintype "passive"))
      (node (ref "SOCKET2") (pin "B8") (pinfunction "PWR_ON#_B8") (pintype "bidirectional"))
    )
    (net (code "81") (name "/PWR_ON#_2") (class "Default")
      (node (ref "IC3") (pin "1") (pinfunction "1A_1") (pintype "bidirectional"))
      (node (ref "RA5") (pin "4") (pinfunction "1_4") (pintype "passive"))
      (node (ref "SOCKET3") (pin "B8") (pinfunction "PWR_ON#_B8") (pintype "bidirectional"))
    )
    (net (code "82") (name "/PWR_ON#_3") (class "Default")
      (node (ref "IC4") (pin "1") (pinfunction "1A_1") (pintype "bidirectional"))
      (node (ref "RA7") (pin "4") (pinfunction "1_4") (pintype "passive"))
      (node (ref "SOCKET4") (pin "B8") (pinfunction "PWR_ON#_B8") (pintype "bidirectional"))
    )
    (net (code "87") (name "/RESET_BUT") (class "Default")
      (node (ref "C13") (pin "1") (pinfunction "1_1") (pintype "passive"))
      (node (ref "R26") (pin "1") (pinfunction "1_1") (pintype "passive"))
      (node (ref "S1") (pin "4") (pinfunction "4_4") (pintype "passive"))
      (node (ref "U$11") (pin "RST_2") (pinfunction "RST2_RST_2") (pintype "bidirectional"))
    )
    (net (code "88") (name "/SPI_CLK_0") (class "Default")
      (node (ref "SOCKET1") (pin "B27") (pinfunction "L7_P_B27") (pintype "bidirectional"))
      (node (ref "U$2") (pin "4") (pinfunction "4_4") (pintype "passive"))
    )
    (net (code "89") (name "/SPI_CLK_1") (class "Default")
      (node (ref "SOCKET2") (pin "B27") (pinfunction "L7_P_B27") (pintype "bidirectional"))
      (node (ref "U$3") (pin "4") (pinfunction "4_4") (pintype "passive"))
    )
    (net (code "90") (name "/SPI_CLK_2") (class "Default")
      (node (ref "SOCKET3") (pin "B27") (pinfunction "L7_P_B27") (pintype "bidirectional"))
      (node (ref "U$4") (pin "4") (pinfunction "4_4") (pintype "passive"))
    )
    (net (code "91") (name "/SPI_CLK_3") (class "Default")
      (node (ref "SOCKET4") (pin "B27") (pinfunction "L7_P_B27") (pintype "bidirectional"))
      (node (ref "U$5") (pin "4") (pinfunction "4_4") (pintype "passive"))
    )
    (net (code "92") (name "/SPI_CS_0") (class "Default")
      (node (ref "SOCKET1") (pin "B28") (pinfunction "L7_N_B28") (pintype "bidirectional"))
      (node (ref "U$2") (pin "3") (pinfunction "3_3") (pintype "passive"))
    )
    (net (code "93") (name "/SPI_CS_1") (class "Default")
      (node (ref "SOCKET2") (pin "B28") (pinfunction "L7_N_B28") (pintype "bidirectional"))
      (node (ref "U$3") (pin "3") (pinfunction "3_3") (pintype "passive"))
    )
    (net (code "94") (name "/SPI_CS_2") (class "Default")
      (node (ref "SOCKET3") (pin "B28") (pinfunction "L7_N_B28") (pintype "bidirectional"))
      (node (ref "U$4") (pin "3") (pinfunction "3_3") (pintype "passive"))
    )
    (net (code "95") (name "/SPI_CS_3") (class "Default")
      (node (ref "SOCKET4") (pin "B28") (pinfunction "L7_N_B28") (pintype "bidirectional"))
      (node (ref "U$5") (pin "3") (pinfunction "3_3") (pintype "passive"))
    )
    (net (code "96") (name "/SPI_MISO_0") (class "Default")
      (node (ref "SOCKET1") (pin "B24") (pinfunction "L5_N_B24") (pintype "bidirectional"))
      (node (ref "U$2") (pin "2") (pinfunction "2_2") (pintype "passive"))
    )
    (net (code "97") (name "/SPI_MISO_1") (class "Default")
      (node (ref "SOCKET2") (pin "B24") (pinfunction "L5_N_B24") (pintype "bidirectional"))
      (node (ref "U$3") (pin "2") (pinfunction "2_2") (pintype "passive"))
    )
    (net (code "98") (name "/SPI_MISO_2") (class "Default")
      (node (ref "SOCKET3") (pin "B24") (pinfunction "L5_N_B24") (pintype "bidirectional"))
      (node (ref "U$4") (pin "2") (pinfunction "2_2") (pintype "passive"))
    )
    (net (code "99") (name "/SPI_MISO_3") (class "Default")
      (node (ref "SOCKET4") (pin "B24") (pinfunction "L5_N_B24") (pintype "bidirectional"))
      (node (ref "U$5") (pin "2") (pinfunction "2_2") (pintype "passive"))
    )
    (net (code "100") (name "/SPI_MOSI_0") (class "Default")
      (node (ref "SOCKET1") (pin "B23") (pinfunction "L5_P_B23") (pintype "bidirectional"))
      (node (ref "U$2") (pin "1") (pinfunction "1_1") (pintype "passive"))
    )
    (net (code "101") (name "/SPI_MOSI_1") (class "Default")
      (node (ref "SOCKET2") (pin "B23") (pinfunction "L5_P_B23") (pintype "bidirectional"))
      (node (ref "U$3") (pin "1") (pinfunction "1_1") (pintype "passive"))
    )
    (net (code "102") (name "/SPI_MOSI_2") (class "Default")
      (node (ref "SOCKET3") (pin "B23") (pinfunction "L5_P_B23") (pintype "bidirectional"))
      (node (ref "U$4") (pin "1") (pinfunction "1_1") (pintype "passive"))
    )
    (net (code "103") (name "/SPI_MOSI_3") (class "Default")
      (node (ref "SOCKET4") (pin "B23") (pinfunction "L5_P_B23") (pintype "bidirectional"))
      (node (ref "U$5") (pin "1") (pinfunction "1_1") (pintype "passive"))
    )
    (net (code "104") (name "/SYS_RESET#_0") (class "Default")
      (node (ref "CONN10") (pin "P") (pinfunction "P_P") (pintype "bidirectional"))
      (node (ref "IC1") (pin "6") (pinfunction "3A_6") (pintype "bidirectional"))
      (node (ref "RA1") (pin "2") (pinfunction "1_2") (pintype "passive"))
      (node (ref "SOCKET1") (pin "B11") (pinfunction "SYS_RESET#_B11") (pintype "bidirectional"))
    )
    (net (code "105") (name "/SYS_RESET#_1") (class "Default")
      (node (ref "IC2") (pin "6") (pinfunction "3A_6") (pintype "bidirectional"))
      (node (ref "RA3") (pin "2") (pinfunction "1_2") (pintype "passive"))
      (node (ref "SOCKET2") (pin "B11") (pinfunction "SYS_RESET#_B11") (pintype "bidirectional"))
    )
    (net (code "106") (name "/SYS_RESET#_2") (class "Default")
      (node (ref "IC3") (pin "6") (pinfunction "3A_6") (pintype "bidirectional"))
      (node (ref "RA5") (pin "2") (pinfunction "1_2") (pintype "passive"))
      (node (ref "SOCKET3") (pin "B11") (pinfunction "SYS_RESET#_B11") (pintype "bidirectional"))
    )
    (net (code "107") (name "/SYS_RESET#_3") (class "Default")
      (node (ref "IC4") (pin "6") (pinfunction "3A_6") (pintype "bidirectional"))
      (node (ref "RA7") (pin "2") (pinfunction "1_2") (pintype "passive"))
      (node (ref "SOCKET4") (pin "B11") (pinfunction "SYS_RESET#_B11") (pintype "bidirectional"))
    )
    (net (code "112") (name "/T_VBUS") (class "Default")
      (node (ref "C28") (pin "1") (pinfunction "+_1") (pintype "passive"))
      (node (ref "CONN5") (pin "P") (pinfunction "P_P") (pintype "bidirectional"))
      (node (ref "R11") (pin "1") (pinfunction "1_1") (pintype "passive"))
      (node (ref "SB12") (pin "R1") (pinfunction "P$2_R1") (pintype "passive"))
      (node (ref "SB12") (pin "R2") (pinfunction "P$2_R2") (pintype "passive"))
      (node (ref "U$15") (pin "TVBUS") (pinfunction "VBUS_TVBUS") (pintype "bidirectional"))
    )
    (net (code "113") (name "/UBOOT_0") (class "Default")
      (node (ref "SOCKET1") (pin "A13") (pinfunction "L0_P_A13") (pintype "bidirectional"))
      (node (ref "U$2") (pin "6") (pinfunction "6_6") (pintype "passive"))
    )
    (net (code "114") (name "/UBOOT_1") (class "Default")
      (node (ref "SOCKET2") (pin "A13") (pinfunction "L0_P_A13") (pintype "bidirectional"))
      (node (ref "U$3") (pin "6") (pinfunction "6_6") (pintype "passive"))
    )
    (net (code "115") (name "/UBOOT_2") (class "Default")
      (node (ref "SOCKET3") (pin "A13") (pinfunction "L0_P_A13") (pintype "bidirectional"))
      (node (ref "U$4") (pin "6") (pinfunction "6_6") (pintype "passive"))
    )
    (net (code "116") (name "/UBOOT_3") (class "Default")
      (node (ref "SOCKET4") (pin "A13") (pinfunction "L0_P_A13") (pintype "bidirectional"))
      (node (ref "U$5") (pin "6") (pinfunction "6_6") (pintype "passive"))
    )
    (net (code "117") (name "/USB_N_2") (class "Default")
      (node (ref "SOCKET2") (pin "B10") (pinfunction "USB_N_B10") (pintype "bidirectional"))
      (node (ref "U$15") (pin "TD-") (pinfunction "D-_TD-") (pintype "bidirectional"))
    )
    (net (code "118") (name "/USB_N_3") (class "Default")
      (node (ref "SOCKET3") (pin "B10") (pinfunction "USB_N_B10") (pintype "bidirectional"))
      (node (ref "U$15") (pin "BD-") (pinfunction "D-_BD-") (pintype "bidirectional"))
    )
    (net (code "119") (name "/USB_P_2") (class "Default")
      (node (ref "SOCKET2") (pin "B9") (pinfunction "USB_P_B9") (pintype "bidirectional"))
      (node (ref "U$15") (pin "TD+") (pinfunction "D+_TD+") (pintype "bidirectional"))
    )
    (net (code "120") (name "/USB_P_3") (class "Default")
      (node (ref "SOCKET3") (pin "B9") (pinfunction "USB_P_B9") (pintype "bidirectional"))
      (node (ref "U$15") (pin "BD+") (pinfunction "D+_BD+") (pintype "bidirectional"))
    )
    (net (code "121") (name "/~{PS_ON}") (class "Default")
      (node (ref "C15") (pin "1") (pinfunction "1_1") (pintype "passive"))
      (node (ref "R28") (pin "1") (pinfunction "1_1") (pintype "passive"))
      (node (ref "U$13") (pin "16") (pinfunction "~{PS_ON}_16") (pintype "bidirectional"))
    )
    (net (code "122") (name "3.3V") (class "Default")
      (node (ref "CONN4") (pin "P$1") (pinfunction "P_P$1") (pintype "bidirectional"))
      (node (ref "IC1") (pin "8") (pinfunction "VCC_8") (pintype "bidirectional"))
      (node (ref "IC2") (pin "8") (pinfunction "VCC_8") (pintype "bidirectional"))
      (node (ref "IC3") (pin "8") (pinfunction "VCC_8") (pintype "bidirectional"))
      (node (ref "IC4") (pin "8") (pinfunction "VCC_8") (pintype "bidirectional"))
      (node (ref "LED0_1") (pin "A") (pinfunction "A_A") (pintype "passive"))
      (node (ref "LED0_2") (pin "A") (pinfunction "A_A") (pintype "passive"))
      (node (ref "LED0_3") (pin "A") (pinfunction "A_A") (pintype "passive"))
      (node (ref "LED0_4") (pin "A") (pinfunction "A_A") (pintype "passive"))
      (node (ref "LED1_1") (pin "A") (pinfunction "A_A") (pintype "passive"))
      (node (ref "LED1_2") (pin "A") (pinfunction "A_A") (pintype "passive"))
      (node (ref "LED1_3") (pin "A") (pinfunction "A_A") (pintype "passive"))
      (node (ref "LED1_4") (pin "A") (pinfunction "A_A") (pintype "passive"))
      (node (ref "LPRSNT_1") (pin "A") (pinfunction "A_A") (pintype "passive"))
      (node (ref "LPRSNT_2") (pin "A") (pinfunction "A_A") (pintype "passive"))
      (node (ref "LPRSNT_3") (pin "A") (pinfunction "A_A") (pintype "passive"))
      (node (ref "LPRSNT_4") (pin "A") (pinfunction "A_A") (pintype "passive"))
      (node (ref "LPWR_ON_1") (pin "A") (pinfunction "A_A") (pintype "passive"))
      (node (ref "LPWR_ON_2") (pin "A") (pinfunction "A_A") (pintype "passive"))
      (node (ref "LPWR_ON_3") (pin "A") (pinfunction "A_A") (pintype "passive"))
      (node (ref "LPWR_ON_4") (pin "A") (pinfunction "A_A") (pintype "passive"))
      (node (ref "LRST_1") (pin "A") (pinfunction "A_A") (pintype "passive"))
      (node (ref "LRST_2") (pin "A") (pinfunction "A_A") (pintype "passive"))
      (node (ref "LRST_3") (pin "A") (pinfunction "A_A") (pintype "passive"))
      (node (ref "LRST_4") (pin "A") (pinfunction "A_A") (pintype "passive"))
      (node (ref "R15") (pin "1") (pinfunction "1_1") (pintype "passive"))
      (node (ref "R16") (pin "1") (pinfunction "1_1") (pintype "passive"))
      (node (ref "R24") (pin "2") (pinfunction "2_2") (pintype "passive"))
      (node (ref "R25") (pin "1") (pinfunction "1_1") (pintype "passive"))
      (node (ref "R28") (pin "2") (pinfunction "2_2") (pintype "passive"))
      (node (ref "RA1") (pin "5") (pinfunction "2_5") (pintype "passive"))
      (node (ref "RA1") (pin "6") (pinfunction "2_6") (pintype "passive"))
      (node (ref "RA1") (pin "7") (pinfunction "2_7") (pintype "passive"))
      (node (ref "RA1") (pin "8") (pinfunction "2_8") (pintype "passive"))
      (node (ref "RA3") (pin "5") (pinfunction "2_5") (pintype "passive"))
      (node (ref "RA3") (pin "6") (pinfunction "2_6") (pintype "passive"))
      (node (ref "RA3") (pin "7") (pinfunction "2_7") (pintype "passive"))
      (node (ref "RA3") (pin "8") (pinfunction "2_8") (pintype "passive"))
      (node (ref "RA5") (pin "5") (pinfunction "2_5") (pintype "passive"))
      (node (ref "RA5") (pin "6") (pinfunction "2_6") (pintype "passive"))
      (node (ref "RA5") (pin "7") (pinfunction "2_7") (pintype "passive"))
      (node (ref "RA5") (pin "8") (pinfunction "2_8") (pintype "passive"))
      (node (ref "RA7") (pin "5") (pinfunction "2_5") (pintype "passive"))
      (node (ref "RA7") (pin "6") (pinfunction "2_6") (pintype "passive"))
      (node (ref "RA7") (pin "7") (pinfunction "2_7") (pintype "passive"))
      (node (ref "RA7") (pin "8") (pinfunction "2_8") (pintype "passive"))
      (node (ref "U$1") (pin "1") (pinfunction "1_1") (pintype "bidirectional"))
      (node (ref "U$1") (pin "2") (pinfunction "2_2") (pintype "bidirectional"))
      (node (ref "U$1") (pin "89") (pinfunction "89_89") (pintype "bidirectional"))
      (node (ref "U$1") (pin "90") (pinfunction "90_90") (pintype "bidirectional"))
      (node (ref "U$13") (pin "1") (pinfunction "3.3V_1") (pintype "bidirectional"))
      (node (ref "U$13") (pin "12") (pinfunction "3.3V_12") (pintype "bidirectional"))
      (node (ref "U$13") (pin "13") (pinfunction "3.3V_13") (pintype "bidirectional"))
      (node (ref "U$13") (pin "2") (pinfunction "3.3V_2") (pintype "bidirectional"))
    )
    (net (code "123") (name "12V") (class "Default")
      (node (ref "C12") (pin "12V") (pinfunction "12V_12V") (pintype "bidirectional"))
      (node (ref "C22") (pin "1") (pinfunction "+_1") (pintype "passive"))
      (node (ref "CONN3") (pin "P$1") (pinfunction "P_P$1") (pintype "bidirectional"))
      (node (ref "R1") (pin "1") (pinfunction "1_1") (pintype "passive"))
      (node (ref "R3") (pin "1") (pinfunction "1_1") (pintype "passive"))
      (node (ref "R5") (pin "1") (pinfunction "1_1") (pintype "passive"))
      (node (ref "R7") (pin "1") (pinfunction "1_1") (pintype "passive"))
      (node (ref "SB1") (pin "L1") (pinfunction "P$1_L1") (pintype "passive"))
      (node (ref "SB1") (pin "L2") (pinfunction "P$1_L2") (pintype "passive"))
      (node (ref "SB3") (pin "L1") (pinfunction "P$1_L1") (pintype "passive"))
      (node (ref "SB3") (pin "L2") (pinfunction "P$1_L2") (pintype "passive"))
      (node (ref "SB5") (pin "L1") (pinfunction "P$1_L1") (pintype "passive"))
      (node (ref "SB5") (pin "L2") (pinfunction "P$1_L2") (pintype "passive"))
      (node (ref "SB7") (pin "L1") (pinfunction "P$1_L1") (pintype "passive"))
      (node (ref "SB7") (pin "L2") (pinfunction "P$1_L2") (pintype "passive"))
      (node (ref "U$13") (pin "10") (pinfunction "12V_10") (pintype "bidirectional"))
      (node (ref "U$13") (pin "11") (pinfunction "12V_11") (pintype "bidirectional"))
    )
    (net (code "124") (name "GND") (class "Default")
      (node (ref "C1") (pin "2") (pinfunction "2_2") (pintype "passive"))
      (node (ref "C12") (pin "GND") (pinfunction "GND_GND") (pintype "bidirectional"))
      (node (ref "C13") (pin "2") (pinfunction "2_2") (pintype "passive"))
      (node (ref "C14") (pin "2") (pinfunction "2_2") (pintype "passive"))
      (node (ref "C15") (pin "2") (pinfunction "2_2") (pintype "passive"))
      (node (ref "C2") (pin "2") (pinfunction "2_2") (pintype "passive"))
      (node (ref "C22") (pin "2") (pinfunction "-_2") (pintype "passive"))
      (node (ref "C28") (pin "2") (pinfunction "-_2") (pintype "passive"))
      (node (ref "C3") (pin "2") (pinfunction "-_2") (pintype "passive"))
      (node (ref "C7") (pin "2") (pinfunction "2_2") (pintype "passive"))
      (node (ref "C8") (pin "2") (pinfunction "2_2") (pintype "passive"))
      (node (ref "CONN2") (pin "P$1") (pinfunction "P_P$1") (pintype "bidirectional"))
      (node (ref "IC1") (pin "4") (pinfunction "GND_4") (pintype "bidirectional"))
      (node (ref "IC2") (pin "4") (pinfunction "GND_4") (pintype "bidirectional"))
      (node (ref "IC3") (pin "4") (pinfunction "GND_4") (pintype "bidirectional"))
      (node (ref "IC4") (pin "4") (pinfunction "GND_4") (pintype "bidirectional"))
      (node (ref "R10") (pin "1") (pinfunction "1_1") (pintype "passive"))
      (node (ref "R12") (pin "1") (pinfunction "1_1") (pintype "passive"))
      (node (ref "S1") (pin "1") (pinfunction "1_1") (pintype "passive"))
      (node (ref "S2") (pin "1") (pinfunction "1_1") (pintype "passive"))
      (node (ref "SB10") (pin "R1") (pinfunction "P$2_R1") (pintype "passive"))
      (node (ref "SB10") (pin "R2") (pinfunction "P$2_R2") (pintype "passive"))
      (node (ref "SB11") (pin "R1") (pinfunction "P$2_R1") (pintype "passive"))
      (node (ref "SB11") (pin "R2") (pinfunction "P$2_R2") (pintype "passive"))
      (node (ref "SB9") (pin "R1") (pinfunction "P$2_R1") (pintype "passive"))
      (node (ref "SB9") (pin "R2") (pinfunction "P$2_R2") (pintype "passive"))
      (node (ref "SOCKET1") (pin "A15") (pinfunction "GND_A15") (pintype "input"))
      (node (ref "SOCKET1") (pin "A16") (pinfunction "GND_A16") (pintype "input"))
      (node (ref "SOCKET1") (pin "A19") (pinfunction "GND_A19") (pintype "input"))
      (node (ref "SOCKET1") (pin "A20") (pinfunction "GND_A20") (pintype "input"))
      (node (ref "SOCKET1") (pin "A23") (pinfunction "GND_A23") (pintype "input"))
      (node (ref "SOCKET1") (pin "A24") (pinfunction "GND_A24") (pintype "input"))
      (node (ref "SOCKET1") (pin "A27") (pinfunction "GND_A27") (pintype "input"))
      (node (ref "SOCKET1") (pin "A28") (pinfunction "GND_A28") (pintype "input"))
      (node (ref "SOCKET1") (pin "A31") (pinfunction "GND_A31") (pintype "input"))
      (node (ref "SOCKET1") (pin "A32") (pinfunction "GND_A32") (pintype "input"))
      (node (ref "SOCKET1") (pin "A35") (pinfunction "GND_A35") (pintype "input"))
      (node (ref "SOCKET1") (pin "A36") (pinfunction "GND_A36") (pintype "input"))
      (node (ref "SOCKET1") (pin "A39") (pinfunction "GND_A39") (pintype "input"))
      (node (ref "SOCKET1") (pin "A4") (pinfunction "GND_A4") (pintype "input"))
      (node (ref "SOCKET1") (pin "A40") (pinfunction "GND_A40") (pintype "input"))
      (node (ref "SOCKET1") (pin "A43") (pinfunction "GND_A43") (pintype "input"))
      (node (ref "SOCKET1") (pin "A44") (pinfunction "GND_A44") (pintype "input"))
      (node (ref "SOCKET1") (pin "A47") (pinfunction "GND_A47") (pintype "input"))
      (node (ref "SOCKET1") (pin "A48") (pinfunction "GND_A48") (pintype "input"))
      (node (ref "SOCKET1") (pin "B13") (pinfunction "GND_B13") (pintype "input"))
      (node (ref "SOCKET1") (pin "B14") (pinfunction "GND_B14") (pintype "input"))
      (node (ref "SOCKET1") (pin "B17") (pinfunction "GND_B17") (pintype "input"))
      (node (ref "SOCKET1") (pin "B18") (pinfunction "GND_B18") (pintype "input"))
      (node (ref "SOCKET1") (pin "B21") (pinfunction "GND_B21") (pintype "input"))
      (node (ref "SOCKET1") (pin "B22") (pinfunction "GND_B22") (pintype "input"))
      (node (ref "SOCKET1") (pin "B25") (pinfunction "GND_B25") (pintype "input"))
      (node (ref "SOCKET1") (pin "B26") (pinfunction "GND_B26") (pintype "input"))
      (node (ref "SOCKET1") (pin "B29") (pinfunction "GND_B29") (pintype "input"))
      (node (ref "SOCKET1") (pin "B30") (pinfunction "GND_B30") (pintype "input"))
      (node (ref "SOCKET1") (pin "B33") (pinfunction "GND_B33") (pintype "input"))
      (node (ref "SOCKET1") (pin "B34") (pinfunction "GND_B34") (pintype "input"))
      (node (ref "SOCKET1") (pin "B37") (pinfunction "GND_B37") (pintype "input"))
      (node (ref "SOCKET1") (pin "B38") (pinfunction "GND_B38") (pintype "input"))
      (node (ref "SOCKET1") (pin "B4") (pinfunction "GND_B4") (pintype "input"))
      (node (ref "SOCKET1") (pin "B41") (pinfunction "GND_B41") (pintype "input"))
      (node (ref "SOCKET1") (pin "B42") (pinfunction "GND_B42") (pintype "input"))
      (node (ref "SOCKET1") (pin "B45") (pinfunction "GND_B45") (pintype "input"))
      (node (ref "SOCKET1") (pin "B46") (pinfunction "GND_B46") (pintype "input"))
      (node (ref "SOCKET1") (pin "B49") (pinfunction "GND/PRSNT2#_B49") (pintype "input"))
      (node (ref "SOCKET1") (pin "B7") (pinfunction "GND_B7") (pintype "input"))
      (node (ref "SOCKET2") (pin "A15") (pinfunction "GND_A15") (pintype "input"))
      (node (ref "SOCKET2") (pin "A16") (pinfunction "GND_A16") (pintype "input"))
      (node (ref "SOCKET2") (pin "A19") (pinfunction "GND_A19") (pintype "input"))
      (node (ref "SOCKET2") (pin "A20") (pinfunction "GND_A20") (pintype "input"))
      (node (ref "SOCKET2") (pin "A23") (pinfunction "GND_A23") (pintype "input"))
      (node (ref "SOCKET2") (pin "A24") (pinfunction "GND_A24") (pintype "input"))
      (node (ref "SOCKET2") (pin "A27") (pinfunction "GND_A27") (pintype "input"))
      (node (ref "SOCKET2") (pin "A28") (pinfunction "GND_A28") (pintype "input"))
      (node (ref "SOCKET2") (pin "A31") (pinfunction "GND_A31") (pintype "input"))
      (node (ref "SOCKET2") (pin "A32") (pinfunction "GND_A32") (pintype "input"))
      (node (ref "SOCKET2") (pin "A35") (pinfunction "GND_A35") (pintype "input"))
      (node (ref "SOCKET2") (pin "A36") (pinfunction "GND_A36") (pintype "input"))
      (node (ref "SOCKET2") (pin "A39") (pinfunction "GND_A39") (pintype "input"))
      (node (ref "SOCKET2") (pin "A4") (pinfunction "GND_A4") (pintype "input"))
      (node (ref "SOCKET2") (pin "A40") (pinfunction "GND_A40") (pintype "input"))
      (node (ref "SOCKET2") (pin "A43") (pinfunction "GND_A43") (pintype "input"))
      (node (ref "SOCKET2") (pin "A44") (pinfunction "GND_A44") (pintype "input"))
      (node (ref "SOCKET2") (pin "A47") (pinfunction "GND_A47") (pintype "input"))
      (node (ref "SOCKET2") (pin "A48") (pinfunction "GND_A48") (pintype "input"))
      (node (ref "SOCKET2") (pin "B13") (pinfunction "GND_B13") (pintype "input"))
      (node (ref "SOCKET2") (pin "B14") (pinfunction "GND_B14") (pintype "input"))
      (node (ref "SOCKET2") (pin "B17") (pinfunction "GND_B17") (pintype "input"))
      (node (ref "SOCKET2") (pin "B18") (pinfunction "GND_B18") (pintype "input"))
      (node (ref "SOCKET2") (pin "B21") (pinfunction "GND_B21") (pintype "input"))
      (node (ref "SOCKET2") (pin "B22") (pinfunction "GND_B22") (pintype "input"))
      (node (ref "SOCKET2") (pin "B25") (pinfunction "GND_B25") (pintype "input"))
      (node (ref "SOCKET2") (pin "B26") (pinfunction "GND_B26") (pintype "input"))
      (node (ref "SOCKET2") (pin "B29") (pinfunction "GND_B29") (pintype "input"))
      (node (ref "SOCKET2") (pin "B30") (pinfunction "GND_B30") (pintype "input"))
      (node (ref "SOCKET2") (pin "B33") (pinfunction "GND_B33") (pintype "input"))
      (node (ref "SOCKET2") (pin "B34") (pinfunction "GND_B34") (pintype "input"))
      (node (ref "SOCKET2") (pin "B37") (pinfunction "GND_B37") (pintype "input"))
      (node (ref "SOCKET2") (pin "B38") (pinfunction "GND_B38") (pintype "input"))
      (node (ref "SOCKET2") (pin "B4") (pinfunction "GND_B4") (pintype "input"))
      (node (ref "SOCKET2") (pin "B41") (pinfunction "GND_B41") (pintype "input"))
      (node (ref "SOCKET2") (pin "B42") (pinfunction "GND_B42") (pintype "input"))
      (node (ref "SOCKET2") (pin "B45") (pinfunction "GND_B45") (pintype "input"))
      (node (ref "SOCKET2") (pin "B46") (pinfunction "GND_B46") (pintype "input"))
      (node (ref "SOCKET2") (pin "B49") (pinfunction "GND/PRSNT2#_B49") (pintype "input"))
      (node (ref "SOCKET2") (pin "B7") (pinfunction "GND_B7") (pintype "input"))
      (node (ref "SOCKET3") (pin "A15") (pinfunction "GND_A15") (pintype "input"))
      (node (ref "SOCKET3") (pin "A16") (pinfunction "GND_A16") (pintype "input"))
      (node (ref "SOCKET3") (pin "A19") (pinfunction "GND_A19") (pintype "input"))
      (node (ref "SOCKET3") (pin "A20") (pinfunction "GND_A20") (pintype "input"))
      (node (ref "SOCKET3") (pin "A23") (pinfunction "GND_A23") (pintype "input"))
      (node (ref "SOCKET3") (pin "A24") (pinfunction "GND_A24") (pintype "input"))
      (node (ref "SOCKET3") (pin "A27") (pinfunction "GND_A27") (pintype "input"))
      (node (ref "SOCKET3") (pin "A28") (pinfunction "GND_A28") (pintype "input"))
      (node (ref "SOCKET3") (pin "A31") (pinfunction "GND_A31") (pintype "input"))
      (node (ref "SOCKET3") (pin "A32") (pinfunction "GND_A32") (pintype "input"))
      (node (ref "SOCKET3") (pin "A35") (pinfunction "GND_A35") (pintype "input"))
      (node (ref "SOCKET3") (pin "A36") (pinfunction "GND_A36") (pintype "input"))
      (node (ref "SOCKET3") (pin "A39") (pinfunction "GND_A39") (pintype "input"))
      (node (ref "SOCKET3") (pin "A4") (pinfunction "GND_A4") (pintype "input"))
      (node (ref "SOCKET3") (pin "A40") (pinfunction "GND_A40") (pintype "input"))
      (node (ref "SOCKET3") (pin "A43") (pinfunction "GND_A43") (pintype "input"))
      (node (ref "SOCKET3") (pin "A44") (pinfunction "GND_A44") (pintype "input"))
      (node (ref "SOCKET3") (pin "A47") (pinfunction "GND_A47") (pintype "input"))
      (node (ref "SOCKET3") (pin "A48") (pinfunction "GND_A48") (pintype "input"))
      (node (ref "SOCKET3") (pin "B13") (pinfunction "GND_B13") (pintype "input"))
      (node (ref "SOCKET3") (pin "B14") (pinfunction "GND_B14") (pintype "input"))
      (node (ref "SOCKET3") (pin "B17") (pinfunction "GND_B17") (pintype "input"))
      (node (ref "SOCKET3") (pin "B18") (pinfunction "GND_B18") (pintype "input"))
      (node (ref "SOCKET3") (pin "B21") (pinfunction "GND_B21") (pintype "input"))
      (node (ref "SOCKET3") (pin "B22") (pinfunction "GND_B22") (pintype "input"))
      (node (ref "SOCKET3") (pin "B25") (pinfunction "GND_B25") (pintype "input"))
      (node (ref "SOCKET3") (pin "B26") (pinfunction "GND_B26") (pintype "input"))
      (node (ref "SOCKET3") (pin "B29") (pinfunction "GND_B29") (pintype "input"))
      (node (ref "SOCKET3") (pin "B30") (pinfunction "GND_B30") (pintype "input"))
      (node (ref "SOCKET3") (pin "B33") (pinfunction "GND_B33") (pintype "input"))
      (node (ref "SOCKET3") (pin "B34") (pinfunction "GND_B34") (pintype "input"))
      (node (ref "SOCKET3") (pin "B37") (pinfunction "GND_B37") (pintype "input"))
      (node (ref "SOCKET3") (pin "B38") (pinfunction "GND_B38") (pintype "input"))
      (node (ref "SOCKET3") (pin "B4") (pinfunction "GND_B4") (pintype "input"))
      (node (ref "SOCKET3") (pin "B41") (pinfunction "GND_B41") (pintype "input"))
      (node (ref "SOCKET3") (pin "B42") (pinfunction "GND_B42") (pintype "input"))
      (node (ref "SOCKET3") (pin "B45") (pinfunction "GND_B45") (pintype "input"))
      (node (ref "SOCKET3") (pin "B46") (pinfunction "GND_B46") (pintype "input"))
      (node (ref "SOCKET3") (pin "B49") (pinfunction "GND/PRSNT2#_B49") (pintype "input"))
      (node (ref "SOCKET3") (pin "B7") (pinfunction "GND_B7") (pintype "input"))
      (node (ref "SOCKET4") (pin "A15") (pinfunction "GND_A15") (pintype "input"))
      (node (ref "SOCKET4") (pin "A16") (pinfunction "GND_A16") (pintype "input"))
      (node (ref "SOCKET4") (pin "A19") (pinfunction "GND_A19") (pintype "input"))
      (node (ref "SOCKET4") (pin "A20") (pinfunction "GND_A20") (pintype "input"))
      (node (ref "SOCKET4") (pin "A23") (pinfunction "GND_A23") (pintype "input"))
      (node (ref "SOCKET4") (pin "A24") (pinfunction "GND_A24") (pintype "input"))
      (node (ref "SOCKET4") (pin "A27") (pinfunction "GND_A27") (pintype "input"))
      (node (ref "SOCKET4") (pin "A28") (pinfunction "GND_A28") (pintype "input"))
      (node (ref "SOCKET4") (pin "A31") (pinfunction "GND_A31") (pintype "input"))
      (node (ref "SOCKET4") (pin "A32") (pinfunction "GND_A32") (pintype "input"))
      (node (ref "SOCKET4") (pin "A35") (pinfunction "GND_A35") (pintype "input"))
      (node (ref "SOCKET4") (pin "A36") (pinfunction "GND_A36") (pintype "input"))
      (node (ref "SOCKET4") (pin "A39") (pinfunction "GND_A39") (pintype "input"))
      (node (ref "SOCKET4") (pin "A4") (pinfunction "GND_A4") (pintype "input"))
      (node (ref "SOCKET4") (pin "A40") (pinfunction "GND_A40") (pintype "input"))
      (node (ref "SOCKET4") (pin "A43") (pinfunction "GND_A43") (pintype "input"))
      (node (ref "SOCKET4") (pin "A44") (pinfunction "GND_A44") (pintype "input"))
      (node (ref "SOCKET4") (pin "A47") (pinfunction "GND_A47") (pintype "input"))
      (node (ref "SOCKET4") (pin "A48") (pinfunction "GND_A48") (pintype "input"))
      (node (ref "SOCKET4") (pin "B13") (pinfunction "GND_B13") (pintype "input"))
      (node (ref "SOCKET4") (pin "B14") (pinfunction "GND_B14") (pintype "input"))
      (node (ref "SOCKET4") (pin "B17") (pinfunction "GND_B17") (pintype "input"))
      (node (ref "SOCKET4") (pin "B18") (pinfunction "GND_B18") (pintype "input"))
      (node (ref "SOCKET4") (pin "B21") (pinfunction "GND_B21") (pintype "input"))
      (node (ref "SOCKET4") (pin "B22") (pinfunction "GND_B22") (pintype "input"))
      (node (ref "SOCKET4") (pin "B25") (pinfunction "GND_B25") (pintype "input"))
      (node (ref "SOCKET4") (pin "B26") (pinfunction "GND_B26") (pintype "input"))
      (node (ref "SOCKET4") (pin "B29") (pinfunction "GND_B29") (pintype "input"))
      (node (ref "SOCKET4") (pin "B30") (pinfunction "GND_B30") (pintype "input"))
      (node (ref "SOCKET4") (pin "B33") (pinfunction "GND_B33") (pintype "input"))
      (node (ref "SOCKET4") (pin "B34") (pinfunction "GND_B34") (pintype "input"))
      (node (ref "SOCKET4") (pin "B37") (pinfunction "GND_B37") (pintype "input"))
      (node (ref "SOCKET4") (pin "B38") (pinfunction "GND_B38") (pintype "input"))
      (node (ref "SOCKET4") (pin "B4") (pinfunction "GND_B4") (pintype "input"))
      (node (ref "SOCKET4") (pin "B41") (pinfunction "GND_B41") (pintype "input"))
      (node (ref "SOCKET4") (pin "B42") (pinfunction "GND_B42") (pintype "input"))
      (node (ref "SOCKET4") (pin "B45") (pinfunction "GND_B45") (pintype "input"))
      (node (ref "SOCKET4") (pin "B46") (pinfunction "GND_B46") (pintype "input"))
      (node (ref "SOCKET4") (pin "B49") (pinfunction "GND/PRSNT2#_B49") (pintype "input"))
      (node (ref "SOCKET4") (pin "B7") (pinfunction "GND_B7") (pintype "input"))
      (node (ref "U$1") (pin "10") (pinfunction "10_10") (pintype "bidirectional"))
      (node (ref "U$1") (pin "14") (pinfunction "14_14") (pintype "bidirectional"))
      (node (ref "U$1") (pin "17") (pinfunction "17_17") (pintype "bidirectional"))
      (node (ref "U$1") (pin "20") (pinfunction "20_20") (pintype "bidirectional"))
      (node (ref "U$1") (pin "24") (pinfunction "24_24") (pintype "bidirectional"))
      (node (ref "U$1") (pin "27") (pinfunction "27_27") (pintype "bidirectional"))
      (node (ref "U$1") (pin "30") (pinfunction "30_30") (pintype "bidirectional"))
      (node (ref "U$1") (pin "34") (pinfunction "34_34") (pintype "bidirectional"))
      (node (ref "U$1") (pin "37") (pinfunction "37_37") (pintype "bidirectional"))
      (node (ref "U$1") (pin "4") (pinfunction "4_4") (pintype "bidirectional"))
      (node (ref "U$1") (pin "40") (pinfunction "40_40") (pintype "bidirectional"))
      (node (ref "U$1") (pin "51") (pinfunction "51_51") (pintype "bidirectional"))
      (node (ref "U$1") (pin "54") (pinfunction "54_54") (pintype "bidirectional"))
      (node (ref "U$1") (pin "57") (pinfunction "57_57") (pintype "bidirectional"))
      (node (ref "U$1") (pin "61") (pinfunction "61_61") (pintype "bidirectional"))
      (node (ref "U$1") (pin "64") (pinfunction "64_64") (pintype "bidirectional"))
      (node (ref "U$1") (pin "67") (pinfunction "67_67") (pintype "bidirectional"))
      (node (ref "U$1") (pin "7") (pinfunction "7_7") (pintype "bidirectional"))
      (node (ref "U$1") (pin "71") (pinfunction "71_71") (pintype "bidirectional"))
      (node (ref "U$1") (pin "74") (pinfunction "74_74") (pintype "bidirectional"))
      (node (ref "U$1") (pin "77") (pinfunction "77_77") (pintype "bidirectional"))
      (node (ref "U$1") (pin "81") (pinfunction "81_81") (pintype "bidirectional"))
      (node (ref "U$1") (pin "84") (pinfunction "84_84") (pintype "bidirectional"))
      (node (ref "U$1") (pin "87") (pinfunction "87_87") (pintype "bidirectional"))
      (node (ref "U$11") (pin "PLED-") (pinfunction "PLED-_PLED-") (pintype "bidirectional"))
      (node (ref "U$11") (pin "PWR_1") (pinfunction "PWR1_PWR_1") (pintype "bidirectional"))
      (node (ref "U$11") (pin "RST_1") (pinfunction "RST1_RST_1") (pintype "bidirectional"))
      (node (ref "U$12") (pin "2") (pinfunction "GND_2") (pintype "bidirectional"))
      (node (ref "U$13") (pin "15") (pinfunction "GND_15") (pintype "bidirectional"))
      (node (ref "U$13") (pin "17") (pinfunction "GND_17") (pintype "bidirectional"))
      (node (ref "U$13") (pin "18") (pinfunction "GND_18") (pintype "bidirectional"))
      (node (ref "U$13") (pin "19") (pinfunction "GND_19") (pintype "bidirectional"))
      (node (ref "U$13") (pin "24") (pinfunction "GND_24") (pintype "bidirectional"))
      (node (ref "U$13") (pin "3") (pinfunction "GND_3") (pintype "bidirectional"))
      (node (ref "U$13") (pin "5") (pinfunction "GND_5") (pintype "bidirectional"))
      (node (ref "U$13") (pin "7") (pinfunction "GND_7") (pintype "bidirectional"))
      (node (ref "U$15") (pin "BGND") (pinfunction "GND_BGND") (pintype "bidirectional"))
      (node (ref "U$15") (pin "TGND") (pinfunction "GND_TGND") (pintype "bidirectional"))
      (node (ref "U$2") (pin "5") (pinfunction "5_5") (pintype "passive"))
      (node (ref "U$3") (pin "5") (pinfunction "5_5") (pintype "passive"))
      (node (ref "U$4") (pin "5") (pinfunction "5_5") (pintype "passive"))
      (node (ref "U$5") (pin "5") (pinfunction "5_5") (pintype "passive"))
      (node (ref "U$6") (pin "2") (pinfunction "GND_2") (pintype "bidirectional"))
    )
    (net (code "125") (name "Net-(C4-Pad2)") (class "Default")
      (node (ref "C4") (pin "2") (pinfunction "2_2") (pintype "passive"))
      (node (ref "U$1") (pin "83") (pinfunction "83_83") (pintype "bidirectional"))
    )
    (net (code "126") (name "Net-(C5-Pad2)") (class "Default")
      (node (ref "C5") (pin "2") (pinfunction "2_2") (pintype "passive"))
      (node (ref "U$1") (pin "82") (pinfunction "82_82") (pintype "bidirectional"))
    )
    (net (code "127") (name "Net-(C6-Pad2)") (class "Default")
      (node (ref "C6") (pin "2") (pinfunction "2_2") (pintype "passive"))
      (node (ref "U$1") (pin "76") (pinfunction "76_76") (pintype "bidirectional"))
    )
    (net (code "128") (name "Net-(C9-Pad2)") (class "Default")
      (node (ref "C9") (pin "2") (pinfunction "2_2") (pintype "passive"))
      (node (ref "U$1") (pin "75") (pinfunction "75_75") (pintype "bidirectional"))
    )
    (net (code "129") (name "Net-(C10-Pad2)") (class "Default")
      (node (ref "C10") (pin "2") (pinfunction "2_2") (pintype "passive"))
      (node (ref "U$1") (pin "73") (pinfunction "73_73") (pintype "bidirectional"))
    )
    (net (code "130") (name "Net-(C11-Pad2)") (class "Default")
      (node (ref "C11") (pin "2") (pinfunction "2_2") (pintype "passive"))
      (node (ref "U$1") (pin "72") (pinfunction "72_72") (pintype "bidirectional"))
    )
    (net (code "131") (name "Net-(C20-Pad2)") (class "Default")
      (node (ref "C20") (pin "2") (pinfunction "2_2") (pintype "passive"))
      (node (ref "U$1") (pin "86") (pinfunction "86_86") (pintype "bidirectional"))
    )
    (net (code "132") (name "Net-(C21-Pad2)") (class "Default")
      (node (ref "C21") (pin "2") (pinfunction "2_2") (pintype "passive"))
      (node (ref "U$1") (pin "85") (pinfunction "85_85") (pintype "bidirectional"))
    )
    (net (code "133") (name "Net-(C23-Pad1)") (class "Default")
      (node (ref "C23") (pin "1") (pinfunction "1_1") (pintype "passive"))
      (node (ref "U$1") (pin "15") (pinfunction "15_15") (pintype "bidirectional"))
    )
    (net (code "134") (name "Net-(C24-Pad1)") (class "Default")
      (node (ref "C24") (pin "1") (pinfunction "1_1") (pintype "passive"))
      (node (ref "U$1") (pin "16") (pinfunction "16_16") (pintype "bidirectional"))
    )
    (net (code "135") (name "Net-(C25-Pad1)") (class "Default")
      (node (ref "C25") (pin "1") (pinfunction "1_1") (pintype "passive"))
      (node (ref "U$1") (pin "18") (pinfunction "18_18") (pintype "bidirectional"))
    )
    (net (code "136") (name "Net-(C26-Pad1)") (class "Default")
      (node (ref "C26") (pin "1") (pinfunction "1_1") (pintype "passive"))
      (node (ref "U$1") (pin "19") (pinfunction "19_19") (pintype "bidirectional"))
    )
    (net (code "137") (name "Net-(C30-Pad1)") (class "Default")
      (node (ref "C30") (pin "1") (pinfunction "1_1") (pintype "passive"))
      (node (ref "U$1") (pin "25") (pinfunction "25_25") (pintype "bidirectional"))
    )
    (net (code "138") (name "Net-(C31-Pad1)") (class "Default")
      (node (ref "C31") (pin "1") (pinfunction "1_1") (pintype "passive"))
      (node (ref "U$1") (pin "26") (pinfunction "26_26") (pintype "bidirectional"))
    )
    (net (code "139") (name "Net-(C32-Pad1)") (class "Default")
      (node (ref "C32") (pin "1") (pinfunction "1_1") (pintype "passive"))
      (node (ref "U$1") (pin "28") (pinfunction "28_28") (pintype "bidirectional"))
    )
    (net (code "140") (name "Net-(C33-Pad1)") (class "Default")
      (node (ref "C33") (pin "1") (pinfunction "1_1") (pintype "passive"))
      (node (ref "U$1") (pin "29") (pinfunction "29_29") (pintype "bidirectional"))
    )
    (net (code "141") (name "Net-(IC1-1Y)") (class "Default")
      (node (ref "IC1") (pin "7") (pinfunction "1Y_7") (pintype "bidirectional"))
      (node (ref "RA2") (pin "3") (pinfunction "1_3") (pintype "passive"))
    )
    (net (code "142") (name "Net-(IC1-2Y)") (class "Default")
      (node (ref "IC1") (pin "5") (pinfunction "2Y_5") (pintype "bidirectional"))
      (node (ref "RA2") (pin "2") (pinfunction "1_2") (pintype "passive"))
    )
    (net (code "143") (name "Net-(IC1-3Y)") (class "Default")
      (node (ref "IC1") (pin "2") (pinfunction "3Y_2") (pintype "bidirectional"))
      (node (ref "RA2") (pin "1") (pinfunction "1_1") (pintype "passive"))
    )
    (net (code "144") (name "Net-(IC2-1Y)") (class "Default")
      (node (ref "IC2") (pin "7") (pinfunction "1Y_7") (pintype "bidirectional"))
      (node (ref "RA4") (pin "3") (pinfunction "1_3") (pintype "passive"))
    )
    (net (code "145") (name "Net-(IC2-2Y)") (class "Default")
      (node (ref "IC2") (pin "5") (pinfunction "2Y_5") (pintype "bidirectional"))
      (node (ref "RA4") (pin "2") (pinfunction "1_2") (pintype "passive"))
    )
    (net (code "146") (name "Net-(IC2-3Y)") (class "Default")
      (node (ref "IC2") (pin "2") (pinfunction "3Y_2") (pintype "bidirectional"))
      (node (ref "RA4") (pin "1") (pinfunction "1_1") (pintype "passive"))
    )
    (net (code "147") (name "Net-(IC3-1Y)") (class "Default")
      (node (ref "IC3") (pin "7") (pinfunction "1Y_7") (pintype "bidirectional"))
      (node (ref "RA6") (pin "3") (pinfunction "1_3") (pintype "passive"))
    )
    (net (code "148") (name "Net-(IC3-2Y)") (class "Default")
      (node (ref "IC3") (pin "5") (pinfunction "2Y_5") (pintype "bidirectional"))
      (node (ref "RA6") (pin "2") (pinfunction "1_2") (pintype "passive"))
    )
    (net (code "149") (name "Net-(IC3-3Y)") (class "Default")
      (node (ref "IC3") (pin "2") (pinfunction "3Y_2") (pintype "bidirectional"))
      (node (ref "RA6") (pin "1") (pinfunction "1_1") (pintype "passive"))
    )
    (net (code "150") (name "Net-(IC4-1Y)") (class "Default")
      (node (ref "IC4") (pin "7") (pinfunction "1Y_7") (pintype "bidirectional"))
      (node (ref "RA8") (pin "3") (pinfunction "1_3") (pintype "passive"))
    )
    (net (code "151") (name "Net-(IC4-2Y)") (class "Default")
      (node (ref "IC4") (pin "5") (pinfunction "2Y_5") (pintype "bidirectional"))
      (node (ref "RA8") (pin "2") (pinfunction "1_2") (pintype "passive"))
    )
    (net (code "152") (name "Net-(IC4-3Y)") (class "Default")
      (node (ref "IC4") (pin "2") (pinfunction "3Y_2") (pintype "bidirectional"))
      (node (ref "RA8") (pin "1") (pinfunction "1_1") (pintype "passive"))
    )
    (net (code "153") (name "Net-(LED0_1-PadC)") (class "Default")
      (node (ref "LED0_1") (pin "C") (pinfunction "C_C") (pintype "passive"))
      (node (ref "R17") (pin "2") (pinfunction "2_2") (pintype "passive"))
    )
    (net (code "154") (name "Net-(LED0_4-PadC)") (class "Default")
      (node (ref "LED0_4") (pin "C") (pinfunction "C_C") (pintype "passive"))
      (node (ref "R21") (pin "2") (pinfunction "2_2") (pintype "passive"))
    )
    (net (code "155") (name "Net-(LED1_1-PadC)") (class "Default")
      (node (ref "LED1_1") (pin "C") (pinfunction "C_C") (pintype "passive"))
      (node (ref "R19") (pin "2") (pinfunction "2_2") (pintype "passive"))
    )
    (net (code "156") (name "Net-(LED1_4-PadC)") (class "Default")
      (node (ref "LED1_4") (pin "C") (pinfunction "C_C") (pintype "passive"))
      (node (ref "R23") (pin "2") (pinfunction "2_2") (pintype "passive"))
    )
    (net (code "157") (name "Net-(R24-Pad1)") (class "Default")
      (node (ref "R24") (pin "1") (pinfunction "1_1") (pintype "passive"))
      (node (ref "U$11") (pin "PLED+") (pinfunction "PLED+_PLED+") (pintype "bidirectional"))
    )
    (net (code "158") (name "Net-(RA2A-2)") (class "Default")
      (node (ref "LRST_1") (pin "C") (pinfunction "C_C") (pintype "passive"))
      (node (ref "RA2") (pin "8") (pinfunction "2_8") (pintype "passive"))
    )
    (net (code "159") (name "Net-(RA2B-2)") (class "Default")
      (node (ref "LPRSNT_1") (pin "C") (pinfunction "C_C") (pintype "passive"))
      (node (ref "RA2") (pin "7") (pinfunction "2_7") (pintype "passive"))
    )
    (net (code "160") (name "Net-(RA2C-2)") (class "Default")
      (node (ref "LPWR_ON_1") (pin "C") (pinfunction "C_C") (pintype "passive"))
      (node (ref "RA2") (pin "6") (pinfunction "2_6") (pintype "passive"))
    )
    (net (code "161") (name "Net-(RA2D-2)") (class "Default")
      (node (ref "LED0_2") (pin "C") (pinfunction "C_C") (pintype "passive"))
      (node (ref "RA2") (pin "5") (pinfunction "2_5") (pintype "passive"))
    )
    (net (code "162") (name "Net-(RA4A-2)") (class "Default")
      (node (ref "LRST_2") (pin "C") (pinfunction "C_C") (pintype "passive"))
      (node (ref "RA4") (pin "8") (pinfunction "2_8") (pintype "passive"))
    )
    (net (code "163") (name "Net-(RA4B-2)") (class "Default")
      (node (ref "LPRSNT_2") (pin "C") (pinfunction "C_C") (pintype "passive"))
      (node (ref "RA4") (pin "7") (pinfunction "2_7") (pintype "passive"))
    )
    (net (code "164") (name "Net-(RA4C-2)") (class "Default")
      (node (ref "LPWR_ON_2") (pin "C") (pinfunction "C_C") (pintype "passive"))
      (node (ref "RA4") (pin "6") (pinfunction "2_6") (pintype "passive"))
    )
    (net (code "165") (name "Net-(RA4D-1)") (class "Default")
      (node (ref "LED1_2") (pin "C") (pinfunction "C_C") (pintype "passive"))
      (node (ref "RA4") (pin "4") (pinfunction "1_4") (pintype "passive"))
    )
    (net (code "166") (name "Net-(RA6A-2)") (class "Default")
      (node (ref "LRST_3") (pin "C") (pinfunction "C_C") (pintype "passive"))
      (node (ref "RA6") (pin "8") (pinfunction "2_8") (pintype "passive"))
    )
    (net (code "167") (name "Net-(RA6B-2)") (class "Default")
      (node (ref "LPRSNT_3") (pin "C") (pinfunction "C_C") (pintype "passive"))
      (node (ref "RA6") (pin "7") (pinfunction "2_7") (pintype "passive"))
    )
    (net (code "168") (name "Net-(RA6C-2)") (class "Default")
      (node (ref "LPWR_ON_3") (pin "C") (pinfunction "C_C") (pintype "passive"))
      (node (ref "RA6") (pin "6") (pinfunction "2_6") (pintype "passive"))
    )
    (net (code "169") (name "Net-(RA6D-1)") (class "Default")
      (node (ref "LED0_3") (pin "C") (pinfunction "C_C") (pintype "passive"))
      (node (ref "RA6") (pin "4") (pinfunction "1_4") (pintype "passive"))
    )
    (net (code "170") (name "Net-(RA8A-2)") (class "Default")
      (node (ref "LRST_4") (pin "C") (pinfunction "C_C") (pintype "passive"))
      (node (ref "RA8") (pin "8") (pinfunction "2_8") (pintype "passive"))
    )
    (net (code "171") (name "Net-(RA8B-2)") (class "Default")
      (node (ref "LPRSNT_4") (pin "C") (pinfunction "C_C") (pintype "passive"))
      (node (ref "RA8") (pin "7") (pinfunction "2_7") (pintype "passive"))
    )
    (net (code "172") (name "Net-(RA8C-2)") (class "Default")
      (node (ref "LPWR_ON_4") (pin "C") (pinfunction "C_C") (pintype "passive"))
      (node (ref "RA8") (pin "6") (pinfunction "2_6") (pintype "passive"))
    )
    (net (code "173") (name "Net-(RA8D-1)") (class "Default")
      (node (ref "LED1_3") (pin "C") (pinfunction "C_C") (pintype "passive"))
      (node (ref "RA8") (pin "4") (pinfunction "1_4") (pintype "passive"))
    )
    (net (code "174") (name "Net-(SOCKET2-SVR_ID0)") (class "Default")
      (node (ref "SB9") (pin "L1") (pinfunction "P$1_L1") (pintype "passive"))
      (node (ref "SB9") (pin "L2") (pinfunction "P$1_L2") (pintype "passive"))
      (node (ref "SOCKET2") (pin "A5") (pinfunction "SVR_ID0_A5") (pintype "bidirectional"))
    )
    (net (code "175") (name "Net-(SOCKET3-SVR_ID1)") (class "Default")
      (node (ref "SB10") (pin "L1") (pinfunction "P$1_L1") (pintype "passive"))
      (node (ref "SB10") (pin "L2") (pinfunction "P$1_L2") (pintype "passive"))
      (node (ref "SOCKET3") (pin "A6") (pinfunction "SVR_ID1_A6") (pintype "bidirectional"))
    )
    (net (code "176") (name "Net-(SOCKET4-SVR_ID0)") (class "Default")
      (node (ref "SB11") (pin "L1") (pinfunction "P$1_L1") (pintype "passive"))
      (node (ref "SB11") (pin "L2") (pinfunction "P$1_L2") (pintype "passive"))
      (node (ref "SOCKET4") (pin "A5") (pinfunction "SVR_ID0_A5") (pintype "bidirectional"))
      (node (ref "SOCKET4") (pin "A6") (pinfunction "SVR_ID1_A6") (pintype "bidirectional"))
    )
    (net (code "177") (name "Net-(U$6-ISET)") (class "Default")
      (node (ref "R10") (pin "2") (pinfunction "2_2") (pintype "passive"))
      (node (ref "U$6") (pin "3") (pinfunction "ISET_3") (pintype "bidirectional"))
    )
    (net (code "178") (name "Net-(U$6-OUT)") (class "Default")
      (node (ref "C8") (pin "1") (pinfunction "1_1") (pintype "passive"))
      (node (ref "R11") (pin "2") (pinfunction "2_2") (pintype "passive"))
      (node (ref "SB12") (pin "L1") (pinfunction "P$1_L1") (pintype "passive"))
      (node (ref "SB12") (pin "L2") (pinfunction "P$1_L2") (pintype "passive"))
      (node (ref "U$6") (pin "1") (pinfunction "OUT_1") (pintype "bidirectional"))
    )
    (net (code "179") (name "Net-(U$11-HLED+)") (class "Default")
      (node (ref "R25") (pin "2") (pinfunction "2_2") (pintype "passive"))
      (node (ref "U$11") (pin "HDLED+") (pinfunction "HLED+_HDLED+") (pintype "bidirectional"))
    )
    (net (code "180") (name "Net-(U$12-ISET)") (class "Default")
      (node (ref "R12") (pin "2") (pinfunction "2_2") (pintype "passive"))
      (node (ref "U$12") (pin "3") (pinfunction "ISET_3") (pintype "bidirectional"))
    )
    (net (code "181") (name "Net-(U$12-OUT)") (class "Default")
      (node (ref "C2") (pin "1") (pinfunction "1_1") (pintype "passive"))
      (node (ref "R13") (pin "2") (pinfunction "2_2") (pintype "passive"))
      (node (ref "SB13") (pin "L1") (pinfunction "P$1_L1") (pintype "passive"))
      (node (ref "SB13") (pin "L2") (pinfunction "P$1_L2") (pintype "passive"))
      (node (ref "U$12") (pin "1") (pinfunction "OUT_1") (pintype "bidirectional"))
    )
    (net (code "182") (name "Net-(U$15A-LGP)") (class "Default")
      (node (ref "R16") (pin "2") (pinfunction "2_2") (pintype "passive"))
      (node (ref "U$15") (pin "R10") (pinfunction "LGP_R10") (pintype "bidirectional"))
    )
    (net (code "183") (name "Net-(U$15A-LYP)") (class "Default")
      (node (ref "R15") (pin "2") (pinfunction "2_2") (pintype "passive"))
      (node (ref "U$15") (pin "R8") (pinfunction "LYP_R8") (pintype "bidirectional"))
    )
    (net (code "184") (name "unconnected-(C12-PadTACH)") (class "Default")
      (node (ref "C12") (pin "TACH") (pinfunction "TACH_TACH") (pintype "bidirectional"))
    )
    (net (code "185") (name "unconnected-(RA1-Pad1)") (class "Default")
      (node (ref "RA1") (pin "1") (pinfunction "1_1") (pintype "passive"))
    )
    (net (code "186") (name "unconnected-(RA3-Pad1)") (class "Default")
      (node (ref "RA3") (pin "1") (pinfunction "1_1") (pintype "passive"))
    )
    (net (code "187") (name "unconnected-(RA5-Pad1)") (class "Default")
      (node (ref "RA5") (pin "1") (pinfunction "1_1") (pintype "passive"))
    )
    (net (code "188") (name "unconnected-(RA7-Pad1)") (class "Default")
      (node (ref "RA7") (pin "1") (pinfunction "1_1") (pintype "passive"))
    )
    (net (code "189") (name "unconnected-(S1-Pad2)") (class "Default")
      (node (ref "S1") (pin "2") (pinfunction "2_2") (pintype "passive"))
    )
    (net (code "190") (name "unconnected-(S1-Pad3)") (class "Default")
      (node (ref "S1") (pin "3") (pinfunction "3_3") (pintype "passive"))
    )
    (net (code "191") (name "unconnected-(S2-Pad2)") (class "Default")
      (node (ref "S2") (pin "2") (pinfunction "2_2") (pintype "passive"))
    )
    (net (code "192") (name "unconnected-(S2-Pad3)") (class "Default")
      (node (ref "S2") (pin "3") (pinfunction "3_3") (pintype "passive"))
    )
    (net (code "193") (name "unconnected-(SOCKET1-GND{slash}SVR_ID4-PadA12)") (class "Default")
      (node (ref "SOCKET1") (pin "A12") (pinfunction "GND/SVR_ID4_A12") (pintype "bidirectional"))
    )
    (net (code "194") (name "unconnected-(SOCKET1-I2C_ALERT#-PadB12)") (class "Default")
      (node (ref "SOCKET1") (pin "B12") (pinfunction "I2C_ALERT#_B12") (pintype "bidirectional"))
    )
    (net (code "195") (name "unconnected-(SOCKET1-L0_N-PadA14)") (class "Default")
      (node (ref "SOCKET1") (pin "A14") (pinfunction "L0_N_A14") (pintype "bidirectional"))
    )
    (net (code "196") (name "unconnected-(SOCKET1-L1_N-PadB16)") (class "Default")
      (node (ref "SOCKET1") (pin "B16") (pinfunction "L1_N_B16") (pintype "bidirectional"))
    )
    (net (code "197") (name "unconnected-(SOCKET1-L1_P-PadB15)") (class "Default")
      (node (ref "SOCKET1") (pin "B15") (pinfunction "L1_P_B15") (pintype "bidirectional"))
    )
    (net (code "198") (name "unconnected-(SOCKET1-L2_N-PadA18)") (class "Default")
      (node (ref "SOCKET1") (pin "A18") (pinfunction "L2_N_A18") (pintype "bidirectional"))
    )
    (net (code "199") (name "unconnected-(SOCKET1-L2_P-PadA17)") (class "Default")
      (node (ref "SOCKET1") (pin "A17") (pinfunction "L2_P_A17") (pintype "bidirectional"))
    )
    (net (code "200") (name "unconnected-(SOCKET1-L3_N-PadB20)") (class "Default")
      (node (ref "SOCKET1") (pin "B20") (pinfunction "L3_N_B20") (pintype "bidirectional"))
    )
    (net (code "201") (name "unconnected-(SOCKET1-L3_P-PadB19)") (class "Default")
      (node (ref "SOCKET1") (pin "B19") (pinfunction "L3_P_B19") (pintype "bidirectional"))
    )
    (net (code "202") (name "unconnected-(SOCKET1-L4_N-PadA22)") (class "Default")
      (node (ref "SOCKET1") (pin "A22") (pinfunction "L4_N_A22") (pintype "bidirectional"))
    )
    (net (code "203") (name "unconnected-(SOCKET1-L4_P-PadA21)") (class "Default")
      (node (ref "SOCKET1") (pin "A21") (pinfunction "L4_P_A21") (pintype "bidirectional"))
    )
    (net (code "204") (name "unconnected-(SOCKET1-L6_N-PadA26)") (class "Default")
      (node (ref "SOCKET1") (pin "A26") (pinfunction "L6_N_A26") (pintype "bidirectional"))
    )
    (net (code "205") (name "unconnected-(SOCKET1-L6_P-PadA25)") (class "Default")
      (node (ref "SOCKET1") (pin "A25") (pinfunction "L6_P_A25") (pintype "bidirectional"))
    )
    (net (code "206") (name "unconnected-(SOCKET1-L8_N-PadA30)") (class "Default")
      (node (ref "SOCKET1") (pin "A30") (pinfunction "L8_N_A30") (pintype "bidirectional"))
    )
    (net (code "207") (name "unconnected-(SOCKET1-L8_P-PadA29)") (class "Default")
      (node (ref "SOCKET1") (pin "A29") (pinfunction "L8_P_A29") (pintype "bidirectional"))
    )
    (net (code "208") (name "unconnected-(SOCKET1-L9_N-PadB32)") (class "Default")
      (node (ref "SOCKET1") (pin "B32") (pinfunction "L9_N_B32") (pintype "bidirectional"))
    )
    (net (code "209") (name "unconnected-(SOCKET1-L9_P-PadB31)") (class "Default")
      (node (ref "SOCKET1") (pin "B31") (pinfunction "L9_P_B31") (pintype "bidirectional"))
    )
    (net (code "210") (name "unconnected-(SOCKET1-L10_N-PadA34)") (class "Default")
      (node (ref "SOCKET1") (pin "A34") (pinfunction "L10_N_A34") (pintype "bidirectional"))
    )
    (net (code "211") (name "unconnected-(SOCKET1-L10_P-PadA33)") (class "Default")
      (node (ref "SOCKET1") (pin "A33") (pinfunction "L10_P_A33") (pintype "bidirectional"))
    )
    (net (code "212") (name "unconnected-(SOCKET1-L11_N-PadB36)") (class "Default")
      (node (ref "SOCKET1") (pin "B36") (pinfunction "L11_N_B36") (pintype "bidirectional"))
    )
    (net (code "213") (name "unconnected-(SOCKET1-L11_P-PadB35)") (class "Default")
      (node (ref "SOCKET1") (pin "B35") (pinfunction "L11_P_B35") (pintype "bidirectional"))
    )
    (net (code "214") (name "unconnected-(SOCKET1-L12_N-PadA38)") (class "Default")
      (node (ref "SOCKET1") (pin "A38") (pinfunction "L12_N_A38") (pintype "bidirectional"))
    )
    (net (code "215") (name "unconnected-(SOCKET1-L12_P-PadA37)") (class "Default")
      (node (ref "SOCKET1") (pin "A37") (pinfunction "L12_P_A37") (pintype "bidirectional"))
    )
    (net (code "216") (name "unconnected-(SOCKET1-L13_N-PadA42)") (class "Default")
      (node (ref "SOCKET1") (pin "A42") (pinfunction "L13_N_A42") (pintype "bidirectional"))
    )
    (net (code "217") (name "unconnected-(SOCKET1-L13_P-PadA41)") (class "Default")
      (node (ref "SOCKET1") (pin "A41") (pinfunction "L13_P_A41") (pintype "bidirectional"))
    )
    (net (code "218") (name "unconnected-(SOCKET1-L14_N-PadA46)") (class "Default")
      (node (ref "SOCKET1") (pin "A46") (pinfunction "L14_N_A46") (pintype "bidirectional"))
    )
    (net (code "219") (name "unconnected-(SOCKET1-L14_P-PadA45)") (class "Default")
      (node (ref "SOCKET1") (pin "A45") (pinfunction "L14_P_A45") (pintype "bidirectional"))
    )
    (net (code "220") (name "unconnected-(SOCKET1-PCIE_RESET#-PadA11)") (class "Default")
      (node (ref "SOCKET1") (pin "A11") (pinfunction "PCIE_RESET#_A11") (pintype "bidirectional"))
    )
    (net (code "221") (name "unconnected-(SOCKET1-RFU-PadA49)") (class "Default")
      (node (ref "SOCKET1") (pin "A49") (pinfunction "RFU_A49") (pintype "no_connect"))
    )
    (net (code "222") (name "unconnected-(SOCKET1-RFU-PadB39)") (class "Default")
      (node (ref "SOCKET1") (pin "B39") (pinfunction "RFU_B39") (pintype "no_connect"))
    )
    (net (code "223") (name "unconnected-(SOCKET1-RFU-PadB40)") (class "Default")
      (node (ref "SOCKET1") (pin "B40") (pinfunction "RFU_B40") (pintype "no_connect"))
    )
    (net (code "224") (name "unconnected-(SOCKET1-SVR_ID0-PadA5)") (class "Default")
      (node (ref "SOCKET1") (pin "A5") (pinfunction "SVR_ID0_A5") (pintype "bidirectional"))
    )
    (net (code "225") (name "unconnected-(SOCKET1-SVR_ID1-PadA6)") (class "Default")
      (node (ref "SOCKET1") (pin "A6") (pinfunction "SVR_ID1_A6") (pintype "bidirectional"))
    )
    (net (code "226") (name "unconnected-(SOCKET1-SVR_ID2-PadA9)") (class "Default")
      (node (ref "SOCKET1") (pin "A9") (pinfunction "SVR_ID2_A9") (pintype "bidirectional"))
    )
    (net (code "227") (name "unconnected-(SOCKET1-SVR_ID3-PadA10)") (class "Default")
      (node (ref "SOCKET1") (pin "A10") (pinfunction "SVR_ID3_A10") (pintype "bidirectional"))
    )
    (net (code "228") (name "unconnected-(SOCKET1-USB_N-PadB10)") (class "Default")
      (node (ref "SOCKET1") (pin "B10") (pinfunction "USB_N_B10") (pintype "bidirectional"))
    )
    (net (code "229") (name "unconnected-(SOCKET1-USB_P-PadB9)") (class "Default")
      (node (ref "SOCKET1") (pin "B9") (pinfunction "USB_P_B9") (pintype "bidirectional"))
    )
    (net (code "230") (name "unconnected-(SOCKET2-GND{slash}SVR_ID4-PadA12)") (class "Default")
      (node (ref "SOCKET2") (pin "A12") (pinfunction "GND/SVR_ID4_A12") (pintype "bidirectional"))
    )
    (net (code "231") (name "unconnected-(SOCKET2-I2C_ALERT#-PadB12)") (class "Default")
      (node (ref "SOCKET2") (pin "B12") (pinfunction "I2C_ALERT#_B12") (pintype "bidirectional"))
    )
    (net (code "232") (name "unconnected-(SOCKET2-L0_N-PadA14)") (class "Default")
      (node (ref "SOCKET2") (pin "A14") (pinfunction "L0_N_A14") (pintype "bidirectional"))
    )
    (net (code "233") (name "unconnected-(SOCKET2-L1_N-PadB16)") (class "Default")
      (node (ref "SOCKET2") (pin "B16") (pinfunction "L1_N_B16") (pintype "bidirectional"))
    )
    (net (code "234") (name "unconnected-(SOCKET2-L1_P-PadB15)") (class "Default")
      (node (ref "SOCKET2") (pin "B15") (pinfunction "L1_P_B15") (pintype "bidirectional"))
    )
    (net (code "235") (name "unconnected-(SOCKET2-L2_N-PadA18)") (class "Default")
      (node (ref "SOCKET2") (pin "A18") (pinfunction "L2_N_A18") (pintype "bidirectional"))
    )
    (net (code "236") (name "unconnected-(SOCKET2-L2_P-PadA17)") (class "Default")
      (node (ref "SOCKET2") (pin "A17") (pinfunction "L2_P_A17") (pintype "bidirectional"))
    )
    (net (code "237") (name "unconnected-(SOCKET2-L3_N-PadB20)") (class "Default")
      (node (ref "SOCKET2") (pin "B20") (pinfunction "L3_N_B20") (pintype "bidirectional"))
    )
    (net (code "238") (name "unconnected-(SOCKET2-L3_P-PadB19)") (class "Default")
      (node (ref "SOCKET2") (pin "B19") (pinfunction "L3_P_B19") (pintype "bidirectional"))
    )
    (net (code "239") (name "unconnected-(SOCKET2-L4_N-PadA22)") (class "Default")
      (node (ref "SOCKET2") (pin "A22") (pinfunction "L4_N_A22") (pintype "bidirectional"))
    )
    (net (code "240") (name "unconnected-(SOCKET2-L4_P-PadA21)") (class "Default")
      (node (ref "SOCKET2") (pin "A21") (pinfunction "L4_P_A21") (pintype "bidirectional"))
    )
    (net (code "241") (name "unconnected-(SOCKET2-L6_N-PadA26)") (class "Default")
      (node (ref "SOCKET2") (pin "A26") (pinfunction "L6_N_A26") (pintype "bidirectional"))
    )
    (net (code "242") (name "unconnected-(SOCKET2-L6_P-PadA25)") (class "Default")
      (node (ref "SOCKET2") (pin "A25") (pinfunction "L6_P_A25") (pintype "bidirectional"))
    )
    (net (code "243") (name "unconnected-(SOCKET2-L8_N-PadA30)") (class "Default")
      (node (ref "SOCKET2") (pin "A30") (pinfunction "L8_N_A30") (pintype "bidirectional"))
    )
    (net (code "244") (name "unconnected-(SOCKET2-L8_P-PadA29)") (class "Default")
      (node (ref "SOCKET2") (pin "A29") (pinfunction "L8_P_A29") (pintype "bidirectional"))
    )
    (net (code "245") (name "unconnected-(SOCKET2-L9_N-PadB32)") (class "Default")
      (node (ref "SOCKET2") (pin "B32") (pinfunction "L9_N_B32") (pintype "bidirectional"))
    )
    (net (code "246") (name "unconnected-(SOCKET2-L9_P-PadB31)") (class "Default")
      (node (ref "SOCKET2") (pin "B31") (pinfunction "L9_P_B31") (pintype "bidirectional"))
    )
    (net (code "247") (name "unconnected-(SOCKET2-L10_N-PadA34)") (class "Default")
      (node (ref "SOCKET2") (pin "A34") (pinfunction "L10_N_A34") (pintype "bidirectional"))
    )
    (net (code "248") (name "unconnected-(SOCKET2-L10_P-PadA33)") (class "Default")
      (node (ref "SOCKET2") (pin "A33") (pinfunction "L10_P_A33") (pintype "bidirectional"))
    )
    (net (code "249") (name "unconnected-(SOCKET2-L11_N-PadB36)") (class "Default")
      (node (ref "SOCKET2") (pin "B36") (pinfunction "L11_N_B36") (pintype "bidirectional"))
    )
    (net (code "250") (name "unconnected-(SOCKET2-L11_P-PadB35)") (class "Default")
      (node (ref "SOCKET2") (pin "B35") (pinfunction "L11_P_B35") (pintype "bidirectional"))
    )
    (net (code "251") (name "unconnected-(SOCKET2-L12_N-PadA38)") (class "Default")
      (node (ref "SOCKET2") (pin "A38") (pinfunction "L12_N_A38") (pintype "bidirectional"))
    )
    (net (code "252") (name "unconnected-(SOCKET2-L12_P-PadA37)") (class "Default")
      (node (ref "SOCKET2") (pin "A37") (pinfunction "L12_P_A37") (pintype "bidirectional"))
    )
    (net (code "253") (name "unconnected-(SOCKET2-L13_N-PadA42)") (class "Default")
      (node (ref "SOCKET2") (pin "A42") (pinfunction "L13_N_A42") (pintype "bidirectional"))
    )
    (net (code "254") (name "unconnected-(SOCKET2-L13_P-PadA41)") (class "Default")
      (node (ref "SOCKET2") (pin "A41") (pinfunction "L13_P_A41") (pintype "bidirectional"))
    )
    (net (code "255") (name "unconnected-(SOCKET2-L14_N-PadA46)") (class "Default")
      (node (ref "SOCKET2") (pin "A46") (pinfunction "L14_N_A46") (pintype "bidirectional"))
    )
    (net (code "256") (name "unconnected-(SOCKET2-L14_P-PadA45)") (class "Default")
      (node (ref "SOCKET2") (pin "A45") (pinfunction "L14_P_A45") (pintype "bidirectional"))
    )
    (net (code "257") (name "unconnected-(SOCKET2-PCIE_RESET#-PadA11)") (class "Default")
      (node (ref "SOCKET2") (pin "A11") (pinfunction "PCIE_RESET#_A11") (pintype "bidirectional"))
    )
    (net (code "258") (name "unconnected-(SOCKET2-RFU-PadA49)") (class "Default")
      (node (ref "SOCKET2") (pin "A49") (pinfunction "RFU_A49") (pintype "no_connect"))
    )
    (net (code "259") (name "unconnected-(SOCKET2-RFU-PadB39)") (class "Default")
      (node (ref "SOCKET2") (pin "B39") (pinfunction "RFU_B39") (pintype "no_connect"))
    )
    (net (code "260") (name "unconnected-(SOCKET2-RFU-PadB40)") (class "Default")
      (node (ref "SOCKET2") (pin "B40") (pinfunction "RFU_B40") (pintype "no_connect"))
    )
    (net (code "261") (name "unconnected-(SOCKET2-SVR_ID1-PadA6)") (class "Default")
      (node (ref "SOCKET2") (pin "A6") (pinfunction "SVR_ID1_A6") (pintype "bidirectional"))
    )
    (net (code "262") (name "unconnected-(SOCKET2-SVR_ID2-PadA9)") (class "Default")
      (node (ref "SOCKET2") (pin "A9") (pinfunction "SVR_ID2_A9") (pintype "bidirectional"))
    )
    (net (code "263") (name "unconnected-(SOCKET2-SVR_ID3-PadA10)") (class "Default")
      (node (ref "SOCKET2") (pin "A10") (pinfunction "SVR_ID3_A10") (pintype "bidirectional"))
    )
    (net (code "264") (name "unconnected-(SOCKET3-GND{slash}SVR_ID4-PadA12)") (class "Default")
      (node (ref "SOCKET3") (pin "A12") (pinfunction "GND/SVR_ID4_A12") (pintype "bidirectional"))
    )
    (net (code "265") (name "unconnected-(SOCKET3-I2C_ALERT#-PadB12)") (class "Default")
      (node (ref "SOCKET3") (pin "B12") (pinfunction "I2C_ALERT#_B12") (pintype "bidirectional"))
    )
    (net (code "266") (name "unconnected-(SOCKET3-L0_N-PadA14)") (class "Default")
      (node (ref "SOCKET3") (pin "A14") (pinfunction "L0_N_A14") (pintype "bidirectional"))
    )
    (net (code "267") (name "unconnected-(SOCKET3-L1_N-PadB16)") (class "Default")
      (node (ref "SOCKET3") (pin "B16") (pinfunction "L1_N_B16") (pintype "bidirectional"))
    )
    (net (code "268") (name "unconnected-(SOCKET3-L1_P-PadB15)") (class "Default")
      (node (ref "SOCKET3") (pin "B15") (pinfunction "L1_P_B15") (pintype "bidirectional"))
    )
    (net (code "269") (name "unconnected-(SOCKET3-L2_N-PadA18)") (class "Default")
      (node (ref "SOCKET3") (pin "A18") (pinfunction "L2_N_A18") (pintype "bidirectional"))
    )
    (net (code "270") (name "unconnected-(SOCKET3-L2_P-PadA17)") (class "Default")
      (node (ref "SOCKET3") (pin "A17") (pinfunction "L2_P_A17") (pintype "bidirectional"))
    )
    (net (code "271") (name "unconnected-(SOCKET3-L3_N-PadB20)") (class "Default")
      (node (ref "SOCKET3") (pin "B20") (pinfunction "L3_N_B20") (pintype "bidirectional"))
    )
    (net (code "272") (name "unconnected-(SOCKET3-L3_P-PadB19)") (class "Default")
      (node (ref "SOCKET3") (pin "B19") (pinfunction "L3_P_B19") (pintype "bidirectional"))
    )
    (net (code "273") (name "unconnected-(SOCKET3-L4_N-PadA22)") (class "Default")
      (node (ref "SOCKET3") (pin "A22") (pinfunction "L4_N_A22") (pintype "bidirectional"))
    )
    (net (code "274") (name "unconnected-(SOCKET3-L4_P-PadA21)") (class "Default")
      (node (ref "SOCKET3") (pin "A21") (pinfunction "L4_P_A21") (pintype "bidirectional"))
    )
    (net (code "275") (name "unconnected-(SOCKET3-L6_N-PadA26)") (class "Default")
      (node (ref "SOCKET3") (pin "A26") (pinfunction "L6_N_A26") (pintype "bidirectional"))
    )
    (net (code "276") (name "unconnected-(SOCKET3-L6_P-PadA25)") (class "Default")
      (node (ref "SOCKET3") (pin "A25") (pinfunction "L6_P_A25") (pintype "bidirectional"))
    )
    (net (code "277") (name "unconnected-(SOCKET3-L8_N-PadA30)") (class "Default")
      (node (ref "SOCKET3") (pin "A30") (pinfunction "L8_N_A30") (pintype "bidirectional"))
    )
    (net (code "278") (name "unconnected-(SOCKET3-L8_P-PadA29)") (class "Default")
      (node (ref "SOCKET3") (pin "A29") (pinfunction "L8_P_A29") (pintype "bidirectional"))
    )
    (net (code "279") (name "unconnected-(SOCKET3-L9_N-PadB32)") (class "Default")
      (node (ref "SOCKET3") (pin "B32") (pinfunction "L9_N_B32") (pintype "bidirectional"))
    )
    (net (code "280") (name "unconnected-(SOCKET3-L9_P-PadB31)") (class "Default")
      (node (ref "SOCKET3") (pin "B31") (pinfunction "L9_P_B31") (pintype "bidirectional"))
    )
    (net (code "281") (name "unconnected-(SOCKET3-L10_N-PadA34)") (class "Default")
      (node (ref "SOCKET3") (pin "A34") (pinfunction "L10_N_A34") (pintype "bidirectional"))
    )
    (net (code "282") (name "unconnected-(SOCKET3-L10_P-PadA33)") (class "Default")
      (node (ref "SOCKET3") (pin "A33") (pinfunction "L10_P_A33") (pintype "bidirectional"))
    )
    (net (code "283") (name "unconnected-(SOCKET3-L11_N-PadB36)") (class "Default")
      (node (ref "SOCKET3") (pin "B36") (pinfunction "L11_N_B36") (pintype "bidirectional"))
    )
    (net (code "284") (name "unconnected-(SOCKET3-L11_P-PadB35)") (class "Default")
      (node (ref "SOCKET3") (pin "B35") (pinfunction "L11_P_B35") (pintype "bidirectional"))
    )
    (net (code "285") (name "unconnected-(SOCKET3-L12_N-PadA38)") (class "Default")
      (node (ref "SOCKET3") (pin "A38") (pinfunction "L12_N_A38") (pintype "bidirectional"))
    )
    (net (code "286") (name "unconnected-(SOCKET3-L12_P-PadA37)") (class "Default")
      (node (ref "SOCKET3") (pin "A37") (pinfunction "L12_P_A37") (pintype "bidirectional"))
    )
    (net (code "287") (name "unconnected-(SOCKET3-L13_N-PadA42)") (class "Default")
      (node (ref "SOCKET3") (pin "A42") (pinfunction "L13_N_A42") (pintype "bidirectional"))
    )
    (net (code "288") (name "unconnected-(SOCKET3-L13_P-PadA41)") (class "Default")
      (node (ref "SOCKET3") (pin "A41") (pinfunction "L13_P_A41") (pintype "bidirectional"))
    )
    (net (code "289") (name "unconnected-(SOCKET3-L14_N-PadA46)") (class "Default")
      (node (ref "SOCKET3") (pin "A46") (pinfunction "L14_N_A46") (pintype "bidirectional"))
    )
    (net (code "290") (name "unconnected-(SOCKET3-L14_P-PadA45)") (class "Default")
      (node (ref "SOCKET3") (pin "A45") (pinfunction "L14_P_A45") (pintype "bidirectional"))
    )
    (net (code "291") (name "unconnected-(SOCKET3-PCIE_RESET#-PadA11)") (class "Default")
      (node (ref "SOCKET3") (pin "A11") (pinfunction "PCIE_RESET#_A11") (pintype "bidirectional"))
    )
    (net (code "292") (name "unconnected-(SOCKET3-RFU-PadA49)") (class "Default")
      (node (ref "SOCKET3") (pin "A49") (pinfunction "RFU_A49") (pintype "no_connect"))
    )
    (net (code "293") (name "unconnected-(SOCKET3-RFU-PadB39)") (class "Default")
      (node (ref "SOCKET3") (pin "B39") (pinfunction "RFU_B39") (pintype "no_connect"))
    )
    (net (code "294") (name "unconnected-(SOCKET3-RFU-PadB40)") (class "Default")
      (node (ref "SOCKET3") (pin "B40") (pinfunction "RFU_B40") (pintype "no_connect"))
    )
    (net (code "295") (name "unconnected-(SOCKET3-SVR_ID0-PadA5)") (class "Default")
      (node (ref "SOCKET3") (pin "A5") (pinfunction "SVR_ID0_A5") (pintype "bidirectional"))
    )
    (net (code "296") (name "unconnected-(SOCKET3-SVR_ID2-PadA9)") (class "Default")
      (node (ref "SOCKET3") (pin "A9") (pinfunction "SVR_ID2_A9") (pintype "bidirectional"))
    )
    (net (code "297") (name "unconnected-(SOCKET3-SVR_ID3-PadA10)") (class "Default")
      (node (ref "SOCKET3") (pin "A10") (pinfunction "SVR_ID3_A10") (pintype "bidirectional"))
    )
    (net (code "298") (name "unconnected-(SOCKET4-GND{slash}SVR_ID4-PadA12)") (class "Default")
      (node (ref "SOCKET4") (pin "A12") (pinfunction "GND/SVR_ID4_A12") (pintype "bidirectional"))
    )
    (net (code "299") (name "unconnected-(SOCKET4-I2C_ALERT#-PadB12)") (class "Default")
      (node (ref "SOCKET4") (pin "B12") (pinfunction "I2C_ALERT#_B12") (pintype "bidirectional"))
    )
    (net (code "300") (name "unconnected-(SOCKET4-L0_N-PadA14)") (class "Default")
      (node (ref "SOCKET4") (pin "A14") (pinfunction "L0_N_A14") (pintype "bidirectional"))
    )
    (net (code "301") (name "unconnected-(SOCKET4-L1_N-PadB16)") (class "Default")
      (node (ref "SOCKET4") (pin "B16") (pinfunction "L1_N_B16") (pintype "bidirectional"))
    )
    (net (code "302") (name "unconnected-(SOCKET4-L1_P-PadB15)") (class "Default")
      (node (ref "SOCKET4") (pin "B15") (pinfunction "L1_P_B15") (pintype "bidirectional"))
    )
    (net (code "303") (name "unconnected-(SOCKET4-L2_N-PadA18)") (class "Default")
      (node (ref "SOCKET4") (pin "A18") (pinfunction "L2_N_A18") (pintype "bidirectional"))
    )
    (net (code "304") (name "unconnected-(SOCKET4-L2_P-PadA17)") (class "Default")
      (node (ref "SOCKET4") (pin "A17") (pinfunction "L2_P_A17") (pintype "bidirectional"))
    )
    (net (code "305") (name "unconnected-(SOCKET4-L3_N-PadB20)") (class "Default")
      (node (ref "SOCKET4") (pin "B20") (pinfunction "L3_N_B20") (pintype "bidirectional"))
    )
    (net (code "306") (name "unconnected-(SOCKET4-L3_P-PadB19)") (class "Default")
      (node (ref "SOCKET4") (pin "B19") (pinfunction "L3_P_B19") (pintype "bidirectional"))
    )
    (net (code "307") (name "unconnected-(SOCKET4-L4_N-PadA22)") (class "Default")
      (node (ref "SOCKET4") (pin "A22") (pinfunction "L4_N_A22") (pintype "bidirectional"))
    )
    (net (code "308") (name "unconnected-(SOCKET4-L4_P-PadA21)") (class "Default")
      (node (ref "SOCKET4") (pin "A21") (pinfunction "L4_P_A21") (pintype "bidirectional"))
    )
    (net (code "309") (name "unconnected-(SOCKET4-L6_N-PadA26)") (class "Default")
      (node (ref "SOCKET4") (pin "A26") (pinfunction "L6_N_A26") (pintype "bidirectional"))
    )
    (net (code "310") (name "unconnected-(SOCKET4-L6_P-PadA25)") (class "Default")
      (node (ref "SOCKET4") (pin "A25") (pinfunction "L6_P_A25") (pintype "bidirectional"))
    )
    (net (code "311") (name "unconnected-(SOCKET4-L8_N-PadA30)") (class "Default")
      (node (ref "SOCKET4") (pin "A30") (pinfunction "L8_N_A30") (pintype "bidirectional"))
    )
    (net (code "312") (name "unconnected-(SOCKET4-L8_P-PadA29)") (class "Default")
      (node (ref "SOCKET4") (pin "A29") (pinfunction "L8_P_A29") (pintype "bidirectional"))
    )
    (net (code "313") (name "unconnected-(SOCKET4-L9_N-PadB32)") (class "Default")
      (node (ref "SOCKET4") (pin "B32") (pinfunction "L9_N_B32") (pintype "bidirectional"))
    )
    (net (code "314") (name "unconnected-(SOCKET4-L9_P-PadB31)") (class "Default")
      (node (ref "SOCKET4") (pin "B31") (pinfunction "L9_P_B31") (pintype "bidirectional"))
    )
    (net (code "315") (name "unconnected-(SOCKET4-L10_N-PadA34)") (class "Default")
      (node (ref "SOCKET4") (pin "A34") (pinfunction "L10_N_A34") (pintype "bidirectional"))
    )
    (net (code "316") (name "unconnected-(SOCKET4-L10_P-PadA33)") (class "Default")
      (node (ref "SOCKET4") (pin "A33") (pinfunction "L10_P_A33") (pintype "bidirectional"))
    )
    (net (code "317") (name "unconnected-(SOCKET4-L11_N-PadB36)") (class "Default")
      (node (ref "SOCKET4") (pin "B36") (pinfunction "L11_N_B36") (pintype "bidirectional"))
    )
    (net (code "318") (name "unconnected-(SOCKET4-L11_P-PadB35)") (class "Default")
      (node (ref "SOCKET4") (pin "B35") (pinfunction "L11_P_B35") (pintype "bidirectional"))
    )
    (net (code "319") (name "unconnected-(SOCKET4-L12_N-PadA38)") (class "Default")
      (node (ref "SOCKET4") (pin "A38") (pinfunction "L12_N_A38") (pintype "bidirectional"))
    )
    (net (code "320") (name "unconnected-(SOCKET4-L12_P-PadA37)") (class "Default")
      (node (ref "SOCKET4") (pin "A37") (pinfunction "L12_P_A37") (pintype "bidirectional"))
    )
    (net (code "321") (name "unconnected-(SOCKET4-L13_N-PadA42)") (class "Default")
      (node (ref "SOCKET4") (pin "A42") (pinfunction "L13_N_A42") (pintype "bidirectional"))
    )
    (net (code "322") (name "unconnected-(SOCKET4-L13_P-PadA41)") (class "Default")
      (node (ref "SOCKET4") (pin "A41") (pinfunction "L13_P_A41") (pintype "bidirectional"))
    )
    (net (code "323") (name "unconnected-(SOCKET4-L14_N-PadA46)") (class "Default")
      (node (ref "SOCKET4") (pin "A46") (pinfunction "L14_N_A46") (pintype "bidirectional"))
    )
    (net (code "324") (name "unconnected-(SOCKET4-L14_P-PadA45)") (class "Default")
      (node (ref "SOCKET4") (pin "A45") (pinfunction "L14_P_A45") (pintype "bidirectional"))
    )
    (net (code "325") (name "unconnected-(SOCKET4-PCIE_RESET#-PadA11)") (class "Default")
      (node (ref "SOCKET4") (pin "A11") (pinfunction "PCIE_RESET#_A11") (pintype "bidirectional"))
    )
    (net (code "326") (name "unconnected-(SOCKET4-RFU-PadA49)") (class "Default")
      (node (ref "SOCKET4") (pin "A49") (pinfunction "RFU_A49") (pintype "no_connect"))
    )
    (net (code "327") (name "unconnected-(SOCKET4-RFU-PadB39)") (class "Default")
      (node (ref "SOCKET4") (pin "B39") (pinfunction "RFU_B39") (pintype "no_connect"))
    )
    (net (code "328") (name "unconnected-(SOCKET4-RFU-PadB40)") (class "Default")
      (node (ref "SOCKET4") (pin "B40") (pinfunction "RFU_B40") (pintype "no_connect"))
    )
    (net (code "329") (name "unconnected-(SOCKET4-SVR_ID2-PadA9)") (class "Default")
      (node (ref "SOCKET4") (pin "A9") (pinfunction "SVR_ID2_A9") (pintype "bidirectional"))
    )
    (net (code "330") (name "unconnected-(SOCKET4-SVR_ID3-PadA10)") (class "Default")
      (node (ref "SOCKET4") (pin "A10") (pinfunction "SVR_ID3_A10") (pintype "bidirectional"))
    )
    (net (code "331") (name "unconnected-(SOCKET4-USB_N-PadB10)") (class "Default")
      (node (ref "SOCKET4") (pin "B10") (pinfunction "USB_N_B10") (pintype "bidirectional"))
    )
    (net (code "332") (name "unconnected-(SOCKET4-USB_P-PadB9)") (class "Default")
      (node (ref "SOCKET4") (pin "B9") (pinfunction "USB_P_B9") (pintype "bidirectional"))
    )
    (net (code "333") (name "unconnected-(U$1-Pad3)") (class "Default")
      (node (ref "U$1") (pin "3") (pinfunction "3_3") (pintype "bidirectional"))
    )
    (net (code "334") (name "unconnected-(U$1-Pad13)") (class "Default")
      (node (ref "U$1") (pin "13") (pinfunction "13_13") (pintype "bidirectional"))
    )
    (net (code "335") (name "unconnected-(U$1-Pad23)") (class "Default")
      (node (ref "U$1") (pin "23") (pinfunction "23_23") (pintype "bidirectional"))
    )
    (net (code "336") (name "unconnected-(U$1-Pad33)") (class "Default")
      (node (ref "U$1") (pin "33") (pinfunction "33_33") (pintype "bidirectional"))
    )
    (net (code "337") (name "unconnected-(U$1-Pad35)") (class "Default")
      (node (ref "U$1") (pin "35") (pinfunction "35_35") (pintype "bidirectional"))
    )
    (net (code "338") (name "unconnected-(U$1-Pad36)") (class "Default")
      (node (ref "U$1") (pin "36") (pinfunction "36_36") (pintype "bidirectional"))
    )
    (net (code "339") (name "unconnected-(U$1-Pad38)") (class "Default")
      (node (ref "U$1") (pin "38") (pinfunction "38_38") (pintype "bidirectional"))
    )
    (net (code "340") (name "unconnected-(U$1-Pad39)") (class "Default")
      (node (ref "U$1") (pin "39") (pinfunction "39_39") (pintype "bidirectional"))
    )
    (net (code "341") (name "unconnected-(U$1-Pad41)") (class "Default")
      (node (ref "U$1") (pin "41") (pinfunction "41_41") (pintype "bidirectional"))
    )
    (net (code "342") (name "unconnected-(U$1-Pad42)") (class "Default")
      (node (ref "U$1") (pin "42") (pinfunction "42_42") (pintype "bidirectional"))
    )
    (net (code "343") (name "unconnected-(U$1-Pad43)") (class "Default")
      (node (ref "U$1") (pin "43") (pinfunction "43_43") (pintype "bidirectional"))
    )
    (net (code "344") (name "unconnected-(U$1-Pad44)") (class "Default")
      (node (ref "U$1") (pin "44") (pinfunction "44_44") (pintype "bidirectional"))
    )
    (net (code "345") (name "unconnected-(U$1-Pad45)") (class "Default")
      (node (ref "U$1") (pin "45") (pinfunction "45_45") (pintype "bidirectional"))
    )
    (net (code "346") (name "unconnected-(U$1-Pad46)") (class "Default")
      (node (ref "U$1") (pin "46") (pinfunction "46_46") (pintype "bidirectional"))
    )
    (net (code "347") (name "unconnected-(U$1-Pad47)") (class "Default")
      (node (ref "U$1") (pin "47") (pinfunction "47_47") (pintype "bidirectional"))
    )
    (net (code "348") (name "unconnected-(U$1-Pad48)") (class "Default")
      (node (ref "U$1") (pin "48") (pinfunction "48_48") (pintype "bidirectional"))
    )
    (net (code "349") (name "unconnected-(U$1-Pad49)") (class "Default")
      (node (ref "U$1") (pin "49") (pinfunction "49_49") (pintype "bidirectional"))
    )
    (net (code "350") (name "unconnected-(U$1-Pad50)") (class "Default")
      (node (ref "U$1") (pin "50") (pinfunction "50_50") (pintype "bidirectional"))
    )
    (net (code "351") (name "unconnected-(U$1-Pad52)") (class "Default")
      (node (ref "U$1") (pin "52") (pinfunction "52_52") (pintype "bidirectional"))
    )
    (net (code "352") (name "unconnected-(U$1-Pad53)") (class "Default")
      (node (ref "U$1") (pin "53") (pinfunction "53_53") (pintype "bidirectional"))
    )
    (net (code "353") (name "unconnected-(U$1-Pad55)") (class "Default")
      (node (ref "U$1") (pin "55") (pinfunction "55_55") (pintype "bidirectional"))
    )
    (net (code "354") (name "unconnected-(U$1-Pad56)") (class "Default")
      (node (ref "U$1") (pin "56") (pinfunction "56_56") (pintype "bidirectional"))
    )
    (net (code "355") (name "unconnected-(U$1-Pad58)") (class "Default")
      (node (ref "U$1") (pin "58") (pinfunction "58_58") (pintype "bidirectional"))
    )
    (net (code "356") (name "unconnected-(U$1-Pad59)") (class "Default")
      (node (ref "U$1") (pin "59") (pinfunction "59_59") (pintype "bidirectional"))
    )
    (net (code "357") (name "unconnected-(U$1-Pad60)") (class "Default")
      (node (ref "U$1") (pin "60") (pinfunction "60_60") (pintype "bidirectional"))
    )
    (net (code "358") (name "unconnected-(U$1-Pad62)") (class "Default")
      (node (ref "U$1") (pin "62") (pinfunction "62_62") (pintype "bidirectional"))
    )
    (net (code "359") (name "unconnected-(U$1-Pad63)") (class "Default")
      (node (ref "U$1") (pin "63") (pinfunction "63_63") (pintype "bidirectional"))
    )
    (net (code "360") (name "unconnected-(U$1-Pad65)") (class "Default")
      (node (ref "U$1") (pin "65") (pinfunction "65_65") (pintype "bidirectional"))
    )
    (net (code "361") (name "unconnected-(U$1-Pad66)") (class "Default")
      (node (ref "U$1") (pin "66") (pinfunction "66_66") (pintype "bidirectional"))
    )
    (net (code "362") (name "unconnected-(U$1-Pad68)") (class "Default")
      (node (ref "U$1") (pin "68") (pinfunction "68_68") (pintype "bidirectional"))
    )
    (net (code "363") (name "unconnected-(U$1-Pad78)") (class "Default")
      (node (ref "U$1") (pin "78") (pinfunction "78_78") (pintype "bidirectional"))
    )
    (net (code "364") (name "unconnected-(U$1-Pad88)") (class "Default")
      (node (ref "U$1") (pin "88") (pinfunction "88_88") (pintype "bidirectional"))
    )
    (net (code "365") (name "unconnected-(U$13--12V-Pad14)") (class "Default")
      (node (ref "U$13") (pin "14") (pinfunction "-12V_14") (pintype "bidirectional"))
    )
    (net (code "366") (name "unconnected-(U$15A-RCT-PadR6)") (class "Default")
      (node (ref "U$15") (pin "R6") (pinfunction "RCT_R6") (pintype "bidirectional"))
    )
    (net (code "367") (name "unconnected-(U$15A-TCT-PadR1)") (class "Default")
      (node (ref "U$15") (pin "R1") (pinfunction "TCT_R1") (pintype "bidirectional"))
    )
    (net (code "368") (name "unconnected-(U$17-Pad1)") (class "Default")
      (node (ref "U$17") (pin "1") (pinfunction "1_1") (pintype "bidirectional"))
    )
    (net (code "369") (name "unconnected-(U$17-Pad2)") (class "Default")
      (node (ref "U$17") (pin "2") (pinfunction "2_2") (pintype "bidirectional"))
    )
    (net (code "370") (name "unconnected-(U$17-Pad3)") (class "Default")
      (node (ref "U$17") (pin "3") (pinfunction "3_3") (pintype "bidirectional"))
    )
    (net (code "371") (name "unconnected-(U$17-Pad4)") (class "Default")
      (node (ref "U$17") (pin "4") (pinfunction "4_4") (pintype "bidirectional"))
    )
    (net (code "372") (name "unconnected-(U$17-Pad5)") (class "Default")
      (node (ref "U$17") (pin "5") (pinfunction "5_5") (pintype "bidirectional"))
    )
    (net (code "373") (name "unconnected-(U$17-Pad6)") (class "Default")
      (node (ref "U$17") (pin "6") (pinfunction "6_6") (pintype "bidirectional"))
    )
    (net (code "374") (name "unconnected-(U$17-Pad7)") (class "Default")
      (node (ref "U$17") (pin "7") (pinfunction "7_7") (pintype "bidirectional"))
    )
    (net (code "375") (name "unconnected-(U$17-Pad8)") (class "Default")
      (node (ref "U$17") (pin "8") (pinfunction "8_8") (pintype "bidirectional"))
    )
    (net (code "376") (name "unconnected-(U$17-Pad9)") (class "Default")
      (node (ref "U$17") (pin "9") (pinfunction "9_9") (pintype "bidirectional"))
    )
    (net (code "377") (name "unconnected-(U$17-Pad10)") (class "Default")
      (node (ref "U$17") (pin "10") (pinfunction "10_10") (pintype "bidirectional"))
    )
    (net (code "378") (name "unconnected-(U$17-Pad11)") (class "Default")
      (node (ref "U$17") (pin "11") (pinfunction "11_11") (pintype "bidirectional"))
    )
    (net (code "379") (name "unconnected-(U$17-Pad12)") (class "Default")
      (node (ref "U$17") (pin "12") (pinfunction "12_12") (pintype "bidirectional"))
    )
    (net (code "380") (name "unconnected-(U$17-Pad13)") (class "Default")
      (node (ref "U$17") (pin "13") (pinfunction "13_13") (pintype "bidirectional"))
    )
    (net (code "381") (name "unconnected-(U$17-Pad14)") (class "Default")
      (node (ref "U$17") (pin "14") (pinfunction "14_14") (pintype "bidirectional"))
    )
    (net (code "382") (name "unconnected-(U$17-Pad15)") (class "Default")
      (node (ref "U$17") (pin "15") (pinfunction "15_15") (pintype "bidirectional"))
    )
    (net (code "383") (name "unconnected-(U$17-Pad16)") (class "Default")
      (node (ref "U$17") (pin "16") (pinfunction "16_16") (pintype "bidirectional"))
    )
    (net (code "384") (name "unconnected-(U$17-Pad17)") (class "Default")
      (node (ref "U$17") (pin "17") (pinfunction "17_17") (pintype "bidirectional"))
    )
    (net (code "385") (name "unconnected-(U$17-Pad18)") (class "Default")
      (node (ref "U$17") (pin "18") (pinfunction "18_18") (pintype "bidirectional"))
    )
    (net (code "386") (name "unconnected-(U$17-Pad19)") (class "Default")
      (node (ref "U$17") (pin "19") (pinfunction "19_19") (pintype "bidirectional"))
    )
    (net (code "387") (name "unconnected-(U$17-Pad20)") (class "Default")
      (node (ref "U$17") (pin "20") (pinfunction "20_20") (pintype "bidirectional"))
    )
    (net (code "388") (name "unconnected-(U$17-Pad21)") (class "Default")
      (node (ref "U$17") (pin "21") (pinfunction "21_21") (pintype "bidirectional"))
    )
    (net (code "389") (name "unconnected-(U$17-Pad22)") (class "Default")
      (node (ref "U$17") (pin "22") (pinfunction "22_22") (pintype "bidirectional"))
    )
    (net (code "390") (name "unconnected-(U$17-Pad23)") (class "Default")
      (node (ref "U$17") (pin "23") (pinfunction "23_23") (pintype "bidirectional"))
    )
    (net (code "391") (name "unconnected-(U$17-Pad24)") (class "Default")
      (node (ref "U$17") (pin "24") (pinfunction "24_24") (pintype "bidirectional"))
    )
    (net (code "392") (name "unconnected-(U$17-Pad25)") (class "Default")
      (node (ref "U$17") (pin "25") (pinfunction "25_25") (pintype "bidirectional"))
    )
    (net (code "393") (name "unconnected-(U$17-Pad26)") (class "Default")
      (node (ref "U$17") (pin "26") (pinfunction "26_26") (pintype "bidirectional"))
    )
    (net (code "394") (name "unconnected-(U$17-Pad27)") (class "Default")
      (node (ref "U$17") (pin "27") (pinfunction "27_27") (pintype "bidirectional"))
    )
    (net (code "395") (name "unconnected-(U$17-Pad28)") (class "Default")
      (node (ref "U$17") (pin "28") (pinfunction "28_28") (pintype "bidirectional"))
    )
    (net (code "396") (name "unconnected-(U$17-Pad29)") (class "Default")
      (node (ref "U$17") (pin "29") (pinfunction "29_29") (pintype "bidirectional"))
    )
    (net (code "397") (name "unconnected-(U$17-Pad30)") (class "Default")
      (node (ref "U$17") (pin "30") (pinfunction "30_30") (pintype "bidirectional"))
    )
    (net (code "398") (name "unconnected-(U$17-Pad31)") (class "Default")
      (node (ref "U$17") (pin "31") (pinfunction "31_31") (pintype "bidirectional"))
    )
    (net (code "399") (name "unconnected-(U$17-Pad32)") (class "Default")
      (node (ref "U$17") (pin "32") (pinfunction "32_32") (pintype "bidirectional"))
    )
    (net (code "400") (name "unconnected-(U$17-Pad33)") (class "Default")
      (node (ref "U$17") (pin "33") (pinfunction "33_33") (pintype "bidirectional"))
    )
    (net (code "401") (name "unconnected-(U$17-Pad34)") (class "Default")
      (node (ref "U$17") (pin "34") (pinfunction "34_34") (pintype "bidirectional"))
    )
    (net (code "402") (name "unconnected-(U$17-Pad35)") (class "Default")
      (node (ref "U$17") (pin "35") (pinfunction "35_35") (pintype "bidirectional"))
    )
    (net (code "403") (name "unconnected-(U$17-Pad36)") (class "Default")
      (node (ref "U$17") (pin "36") (pinfunction "36_36") (pintype "bidirectional"))
    )
    (net (code "404") (name "unconnected-(U$17-Pad37)") (class "Default")
      (node (ref "U$17") (pin "37") (pinfunction "37_37") (pintype "bidirectional"))
    )
    (net (code "405") (name "unconnected-(U$17-Pad38)") (class "Default")
      (node (ref "U$17") (pin "38") (pinfunction "38_38") (pintype "bidirectional"))
    )
    (net (code "406") (name "unconnected-(U$17-Pad39)") (class "Default")
      (node (ref "U$17") (pin "39") (pinfunction "39_39") (pintype "bidirectional"))
    )
    (net (code "407") (name "unconnected-(U$17-Pad40)") (class "Default")
      (node (ref "U$17") (pin "40") (pinfunction "40_40") (pintype "bidirectional"))
    )
    (net (code "408") (name "unconnected-(U$17-Pad41)") (class "Default")
      (node (ref "U$17") (pin "41") (pinfunction "41_41") (pintype "bidirectional"))
    )
    (net (code "409") (name "unconnected-(U$17-Pad42)") (class "Default")
      (node (ref "U$17") (pin "42") (pinfunction "42_42") (pintype "bidirectional"))
    )
    (net (code "410") (name "unconnected-(U$17-Pad43)") (class "Default")
      (node (ref "U$17") (pin "43") (pinfunction "43_43") (pintype "bidirectional"))
    )
    (net (code "411") (name "unconnected-(U$17-Pad44)") (class "Default")
      (node (ref "U$17") (pin "44") (pinfunction "44_44") (pintype "bidirectional"))
    )
    (net (code "412") (name "unconnected-(U$17-Pad45)") (class "Default")
      (node (ref "U$17") (pin "45") (pinfunction "45_45") (pintype "bidirectional"))
    )
    (net (code "413") (name "unconnected-(U$17-Pad46)") (class "Default")
      (node (ref "U$17") (pin "46") (pinfunction "46_46") (pintype "bidirectional"))
    )
    (net (code "414") (name "unconnected-(U$17-Pad47)") (class "Default")
      (node (ref "U$17") (pin "47") (pinfunction "47_47") (pintype "bidirectional"))
    )
    (net (code "415") (name "unconnected-(U$17-Pad48)") (class "Default")
      (node (ref "U$17") (pin "48") (pinfunction "48_48") (pintype "bidirectional"))
    )
    (net (code "416") (name "unconnected-(U$17-Pad49)") (class "Default")
      (node (ref "U$17") (pin "49") (pinfunction "49_49") (pintype "bidirectional"))
    )
    (net (code "417") (name "unconnected-(U$17-Pad50)") (class "Default")
      (node (ref "U$17") (pin "50") (pinfunction "50_50") (pintype "bidirectional"))
    )
    (net (code "418") (name "unconnected-(U$17-Pad51)") (class "Default")
      (node (ref "U$17") (pin "51") (pinfunction "51_51") (pintype "bidirectional"))
    )
    (net (code "419") (name "unconnected-(U$17-Pad52)") (class "Default")
      (node (ref "U$17") (pin "52") (pinfunction "52_52") (pintype "bidirectional"))
    )
    (net (code "420") (name "unconnected-(U$17-Pad53)") (class "Default")
      (node (ref "U$17") (pin "53") (pinfunction "53_53") (pintype "bidirectional"))
    )
    (net (code "421") (name "unconnected-(U$17-Pad54)") (class "Default")
      (node (ref "U$17") (pin "54") (pinfunction "54_54") (pintype "bidirectional"))
    )
    (net (code "422") (name "unconnected-(U$17-Pad55)") (class "Default")
      (node (ref "U$17") (pin "55") (pinfunction "55_55") (pintype "bidirectional"))
    )
    (net (code "423") (name "unconnected-(U$17-Pad56)") (class "Default")
      (node (ref "U$17") (pin "56") (pinfunction "56_56") (pintype "bidirectional"))
    )
    (net (code "424") (name "unconnected-(U$17-Pad57)") (class "Default")
      (node (ref "U$17") (pin "57") (pinfunction "57_57") (pintype "bidirectional"))
    )
    (net (code "425") (name "unconnected-(U$17-Pad58)") (class "Default")
      (node (ref "U$17") (pin "58") (pinfunction "58_58") (pintype "bidirectional"))
    )
    (net (code "426") (name "unconnected-(U$17-Pad59)") (class "Default")
      (node (ref "U$17") (pin "59") (pinfunction "59_59") (pintype "bidirectional"))
    )
    (net (code "427") (name "unconnected-(U$17-Pad60)") (class "Default")
      (node (ref "U$17") (pin "60") (pinfunction "60_60") (pintype "bidirectional"))
    )
    (net (code "428") (name "unconnected-(U$17-Pad61)") (class "Default")
      (node (ref "U$17") (pin "61") (pinfunction "61_61") (pintype "bidirectional"))
    )
    (net (code "429") (name "unconnected-(U$17-Pad62)") (class "Default")
      (node (ref "U$17") (pin "62") (pinfunction "62_62") (pintype "bidirectional"))
    )
    (net (code "430") (name "unconnected-(U$17-Pad63)") (class "Default")
      (node (ref "U$17") (pin "63") (pinfunction "63_63") (pintype "bidirectional"))
    )
    (net (code "431") (name "unconnected-(U$17-Pad64)") (class "Default")
      (node (ref "U$17") (pin "64") (pinfunction "64_64") (pintype "bidirectional"))
    )
    (net (code "432") (name "unconnected-(U$17-Pad65)") (class "Default")
      (node (ref "U$17") (pin "65") (pinfunction "65_65") (pintype "bidirectional"))
    )
    (net (code "433") (name "unconnected-(U$17-Pad66)") (class "Default")
      (node (ref "U$17") (pin "66") (pinfunction "66_66") (pintype "bidirectional"))
    )
    (net (code "434") (name "unconnected-(U$17-Pad67)") (class "Default")
      (node (ref "U$17") (pin "67") (pinfunction "67_67") (pintype "bidirectional"))
    )
    (net (code "435") (name "unconnected-(U$17-Pad68)") (class "Default")
      (node (ref "U$17") (pin "68") (pinfunction "68_68") (pintype "bidirectional"))
    )
    (net (code "436") (name "unconnected-(U$17-Pad69)") (class "Default")
      (node (ref "U$17") (pin "69") (pinfunction "69_69") (pintype "bidirectional"))
    )
    (net (code "437") (name "unconnected-(U$17-Pad70)") (class "Default")
      (node (ref "U$17") (pin "70") (pinfunction "70_70") (pintype "bidirectional"))
    )
    (net (code "438") (name "unconnected-(U$17-Pad71)") (class "Default")
      (node (ref "U$17") (pin "71") (pinfunction "71_71") (pintype "bidirectional"))
    )
    (net (code "439") (name "unconnected-(U$17-Pad72)") (class "Default")
      (node (ref "U$17") (pin "72") (pinfunction "72_72") (pintype "bidirectional"))
    )
    (net (code "440") (name "unconnected-(U$17-Pad73)") (class "Default")
      (node (ref "U$17") (pin "73") (pinfunction "73_73") (pintype "bidirectional"))
    )
    (net (code "441") (name "unconnected-(U$17-Pad74)") (class "Default")
      (node (ref "U$17") (pin "74") (pinfunction "74_74") (pintype "bidirectional"))
    )
    (net (code "442") (name "unconnected-(U$17-Pad75)") (class "Default")
      (node (ref "U$17") (pin "75") (pinfunction "75_75") (pintype "bidirectional"))
    )
    (net (code "443") (name "unconnected-(U$17-Pad76)") (class "Default")
      (node (ref "U$17") (pin "76") (pinfunction "76_76") (pintype "bidirectional"))
    )
    (net (code "444") (name "unconnected-(U$17-Pad77)") (class "Default")
      (node (ref "U$17") (pin "77") (pinfunction "77_77") (pintype "bidirectional"))
    )
    (net (code "445") (name "unconnected-(U$17-Pad78)") (class "Default")
      (node (ref "U$17") (pin "78") (pinfunction "78_78") (pintype "bidirectional"))
    )
    (net (code "446") (name "unconnected-(U$17-Pad79)") (class "Default")
      (node (ref "U$17") (pin "79") (pinfunction "79_79") (pintype "bidirectional"))
    )
    (net (code "447") (name "unconnected-(U$17-Pad80)") (class "Default")
      (node (ref "U$17") (pin "80") (pinfunction "80_80") (pintype "bidirectional"))
    )
  )
)
